# axiom_beta_plugin_module_TE0714_SDI_v0_9.net
KiCad netlist of a schematic drawn in EAGLE
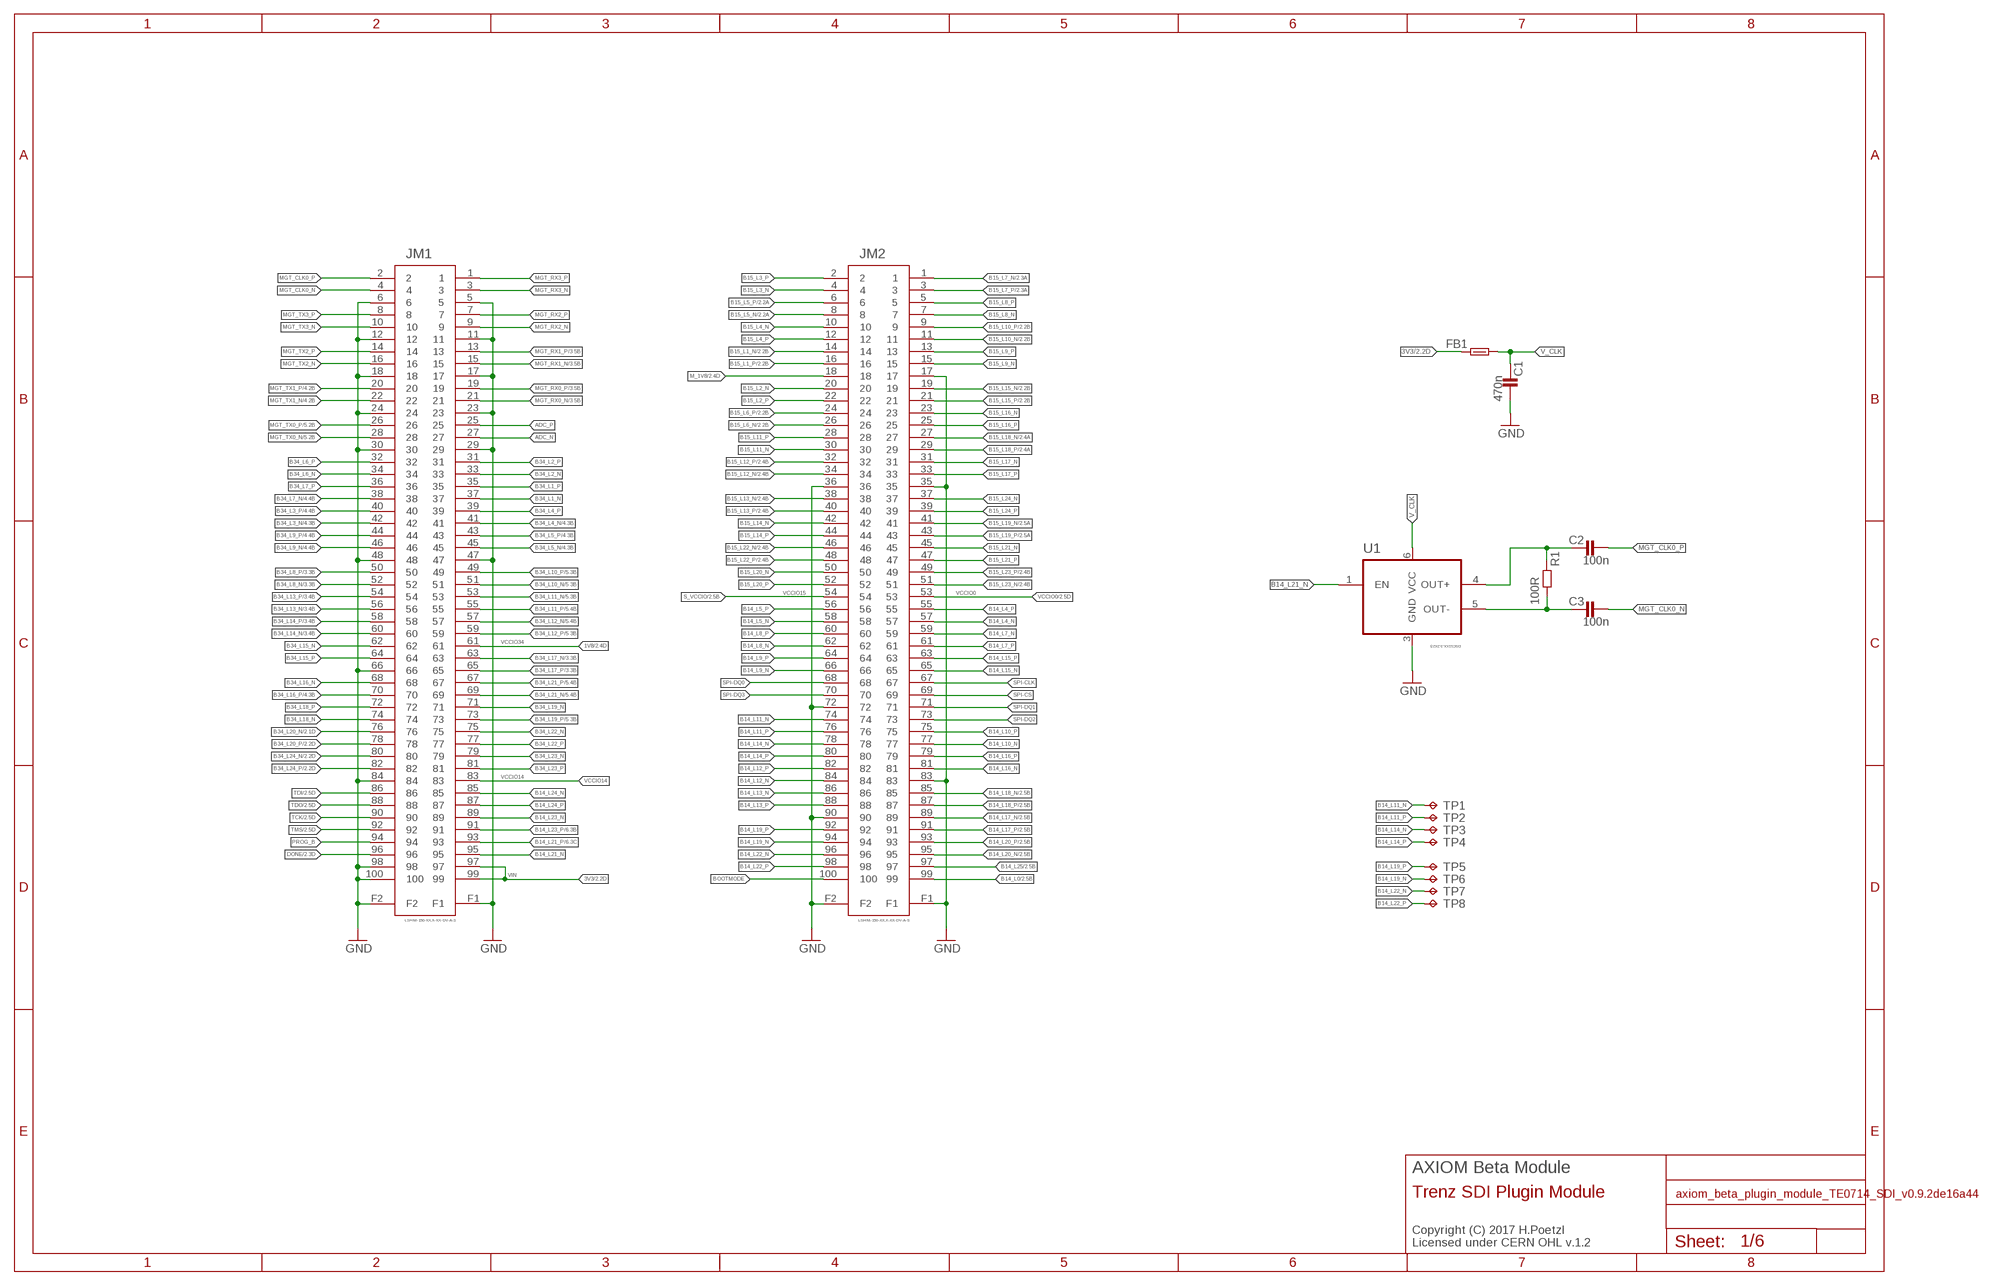
[diagram p0: schematic, sheet 1]
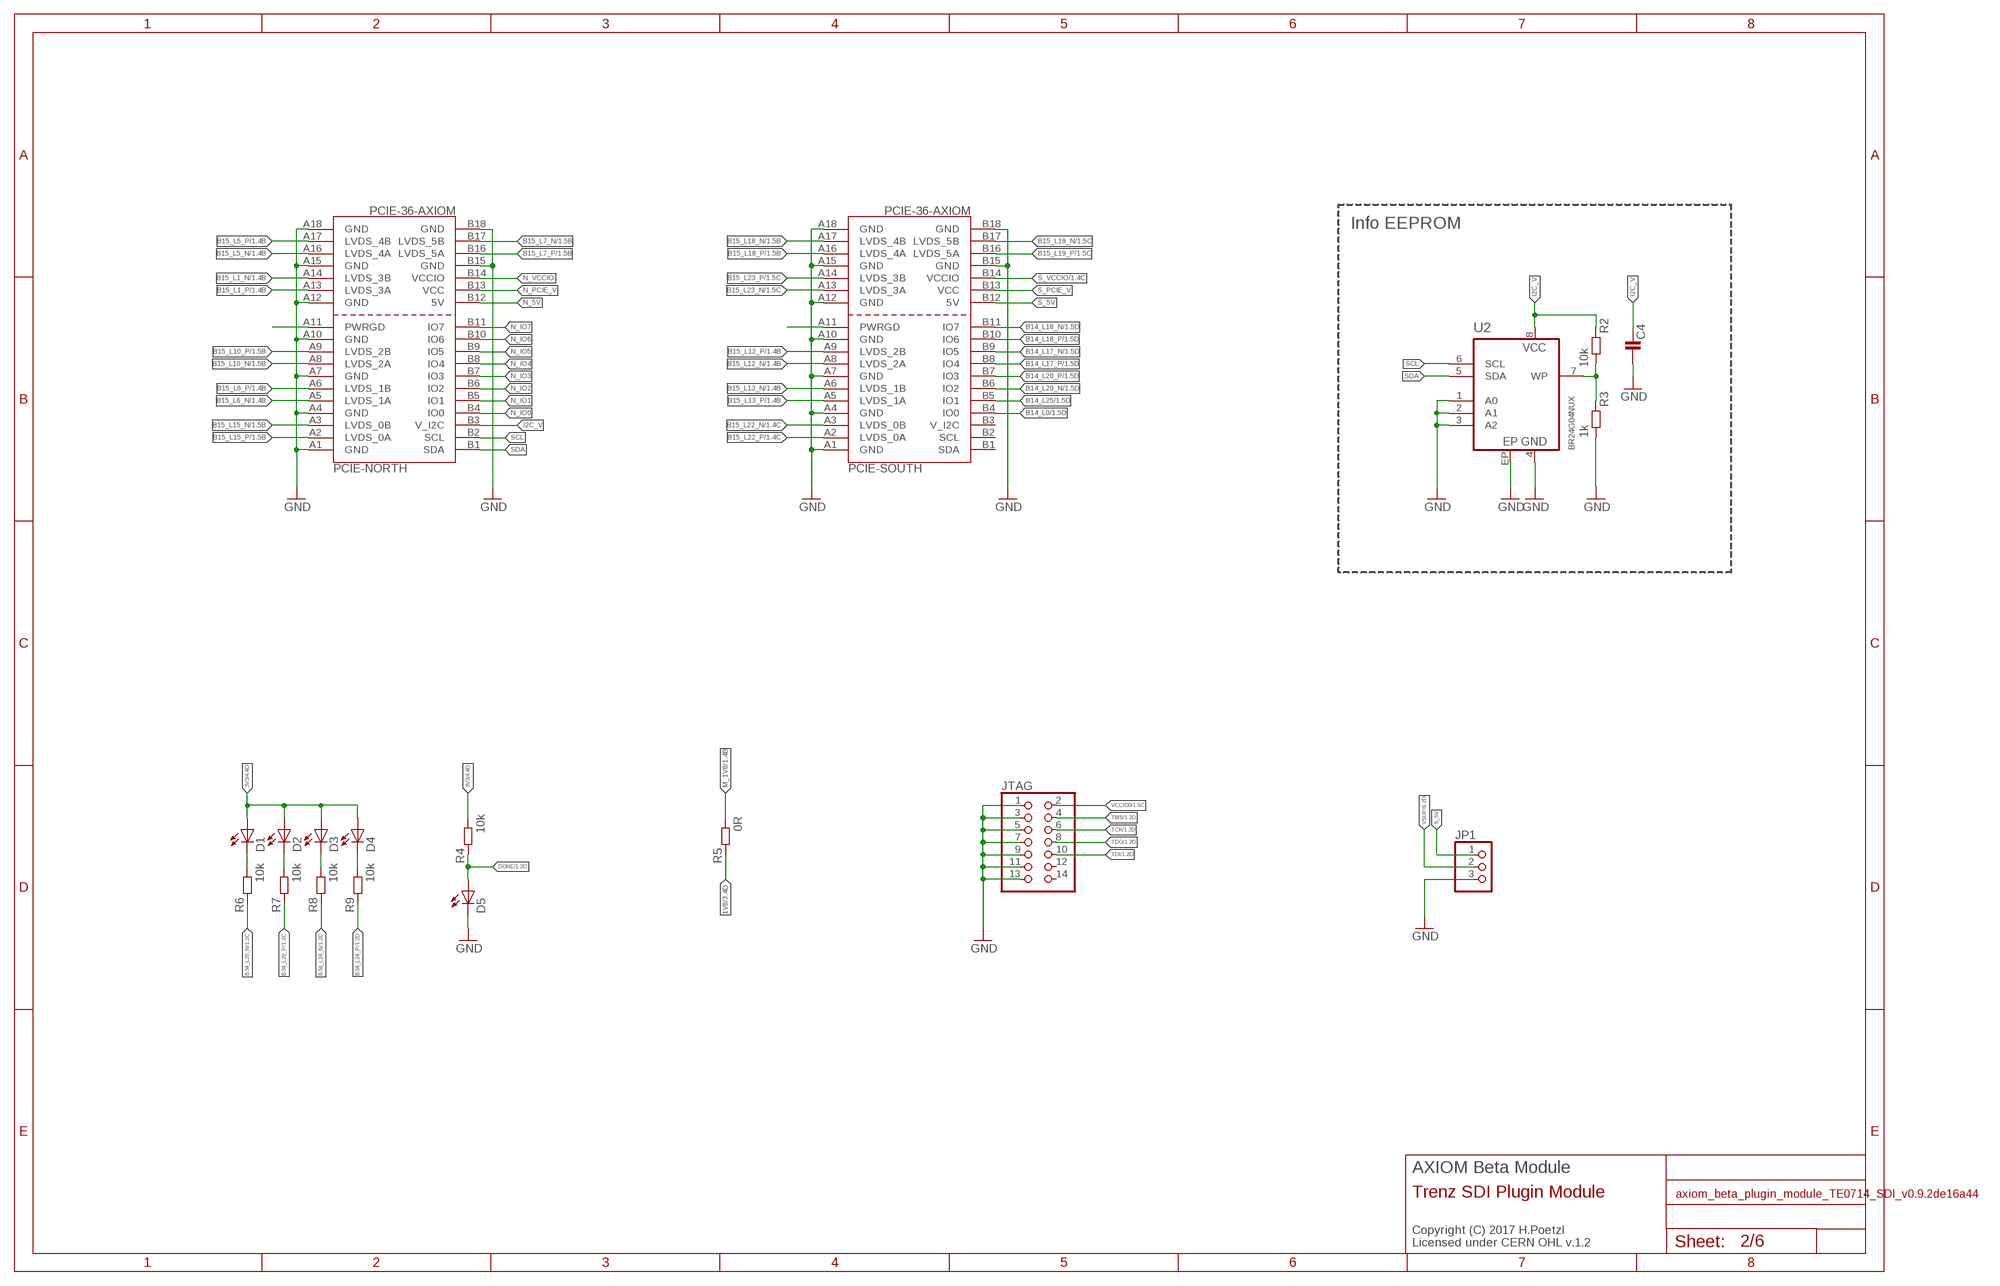
[diagram p1: schematic, sheet 2]
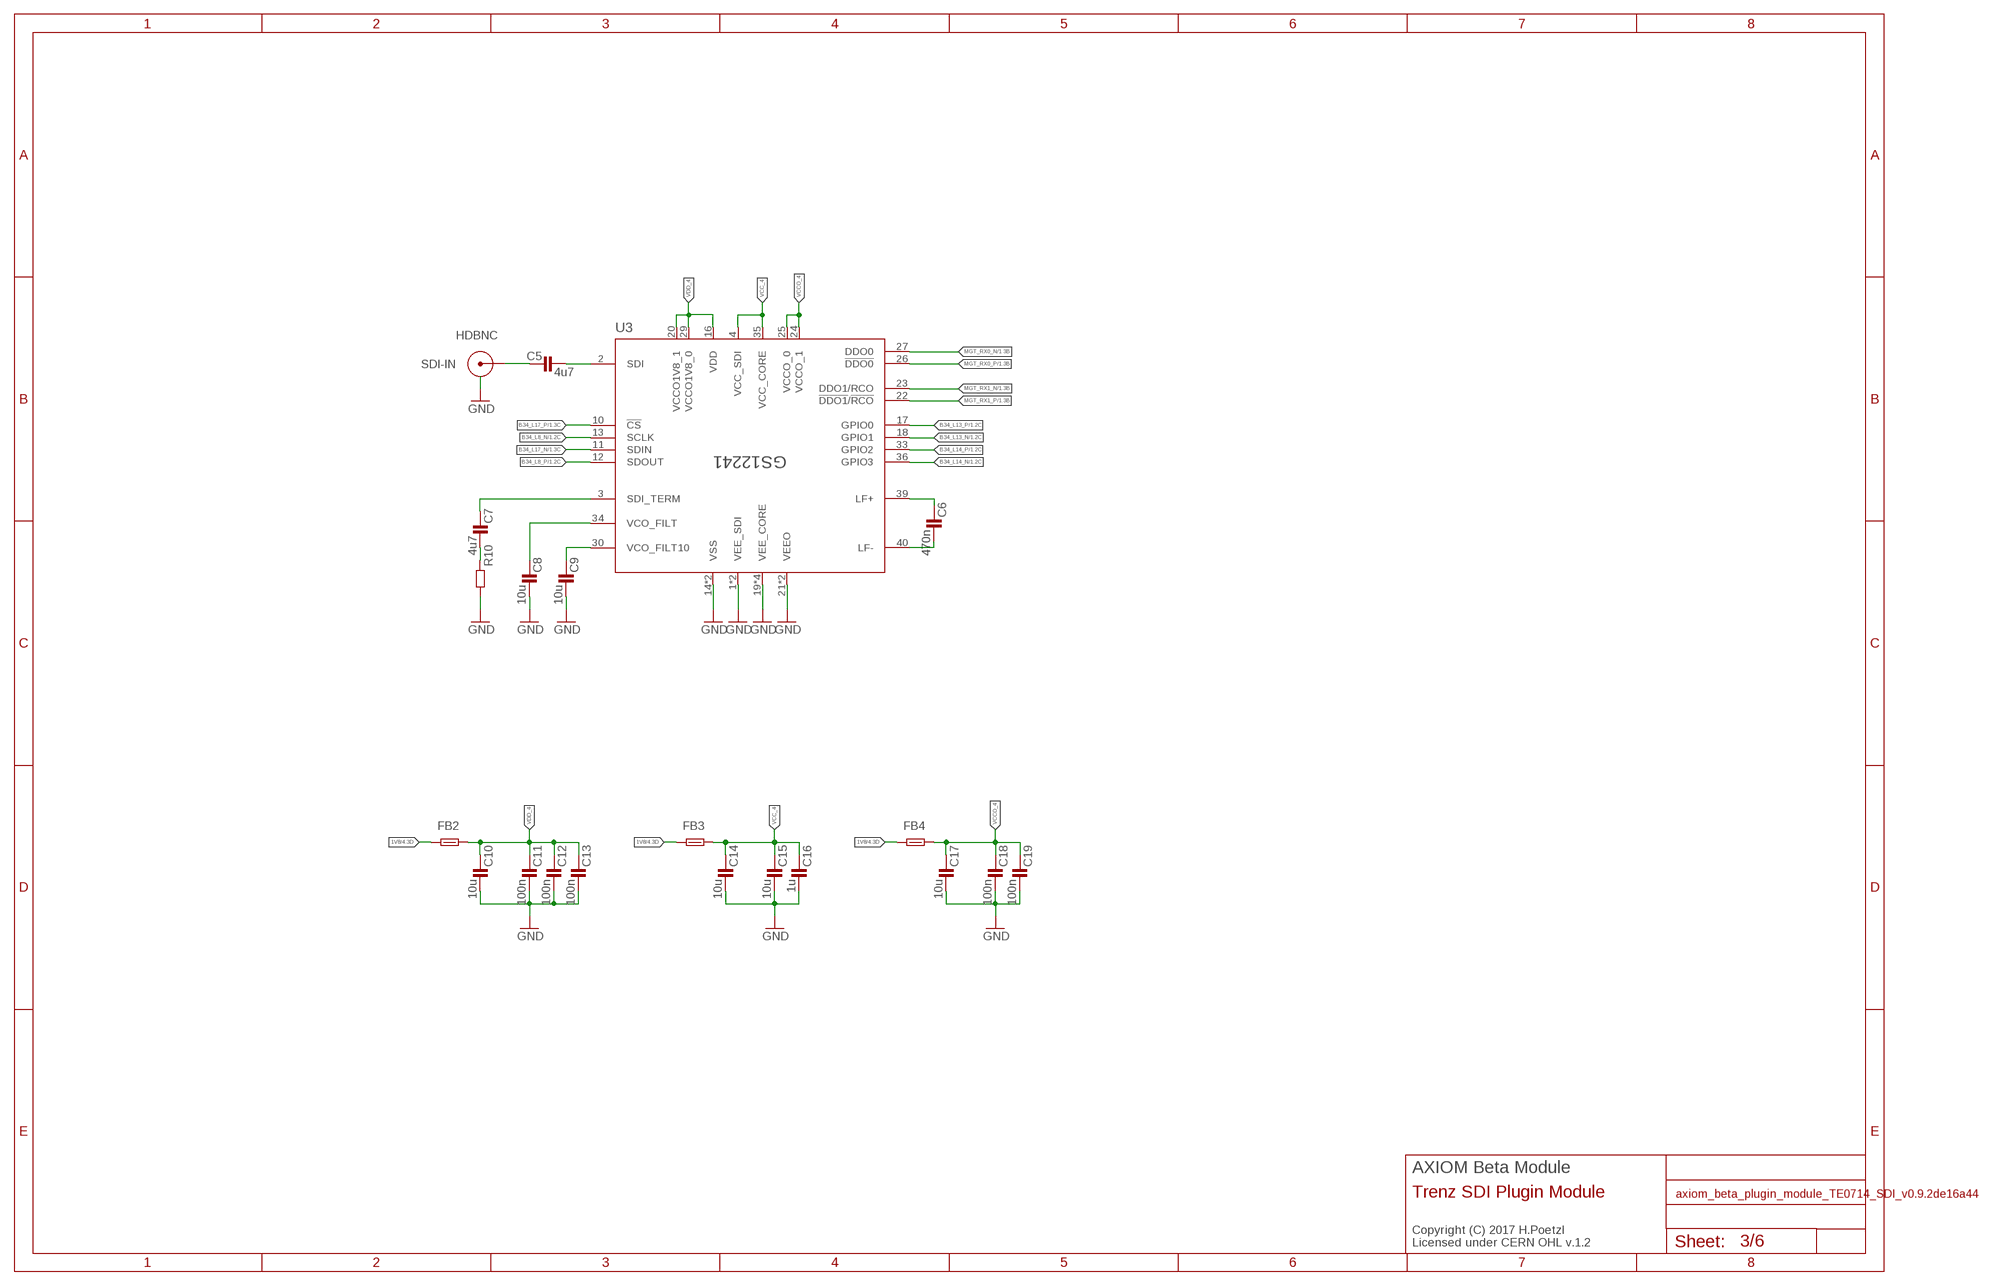
[diagram p2: schematic, sheet 3]
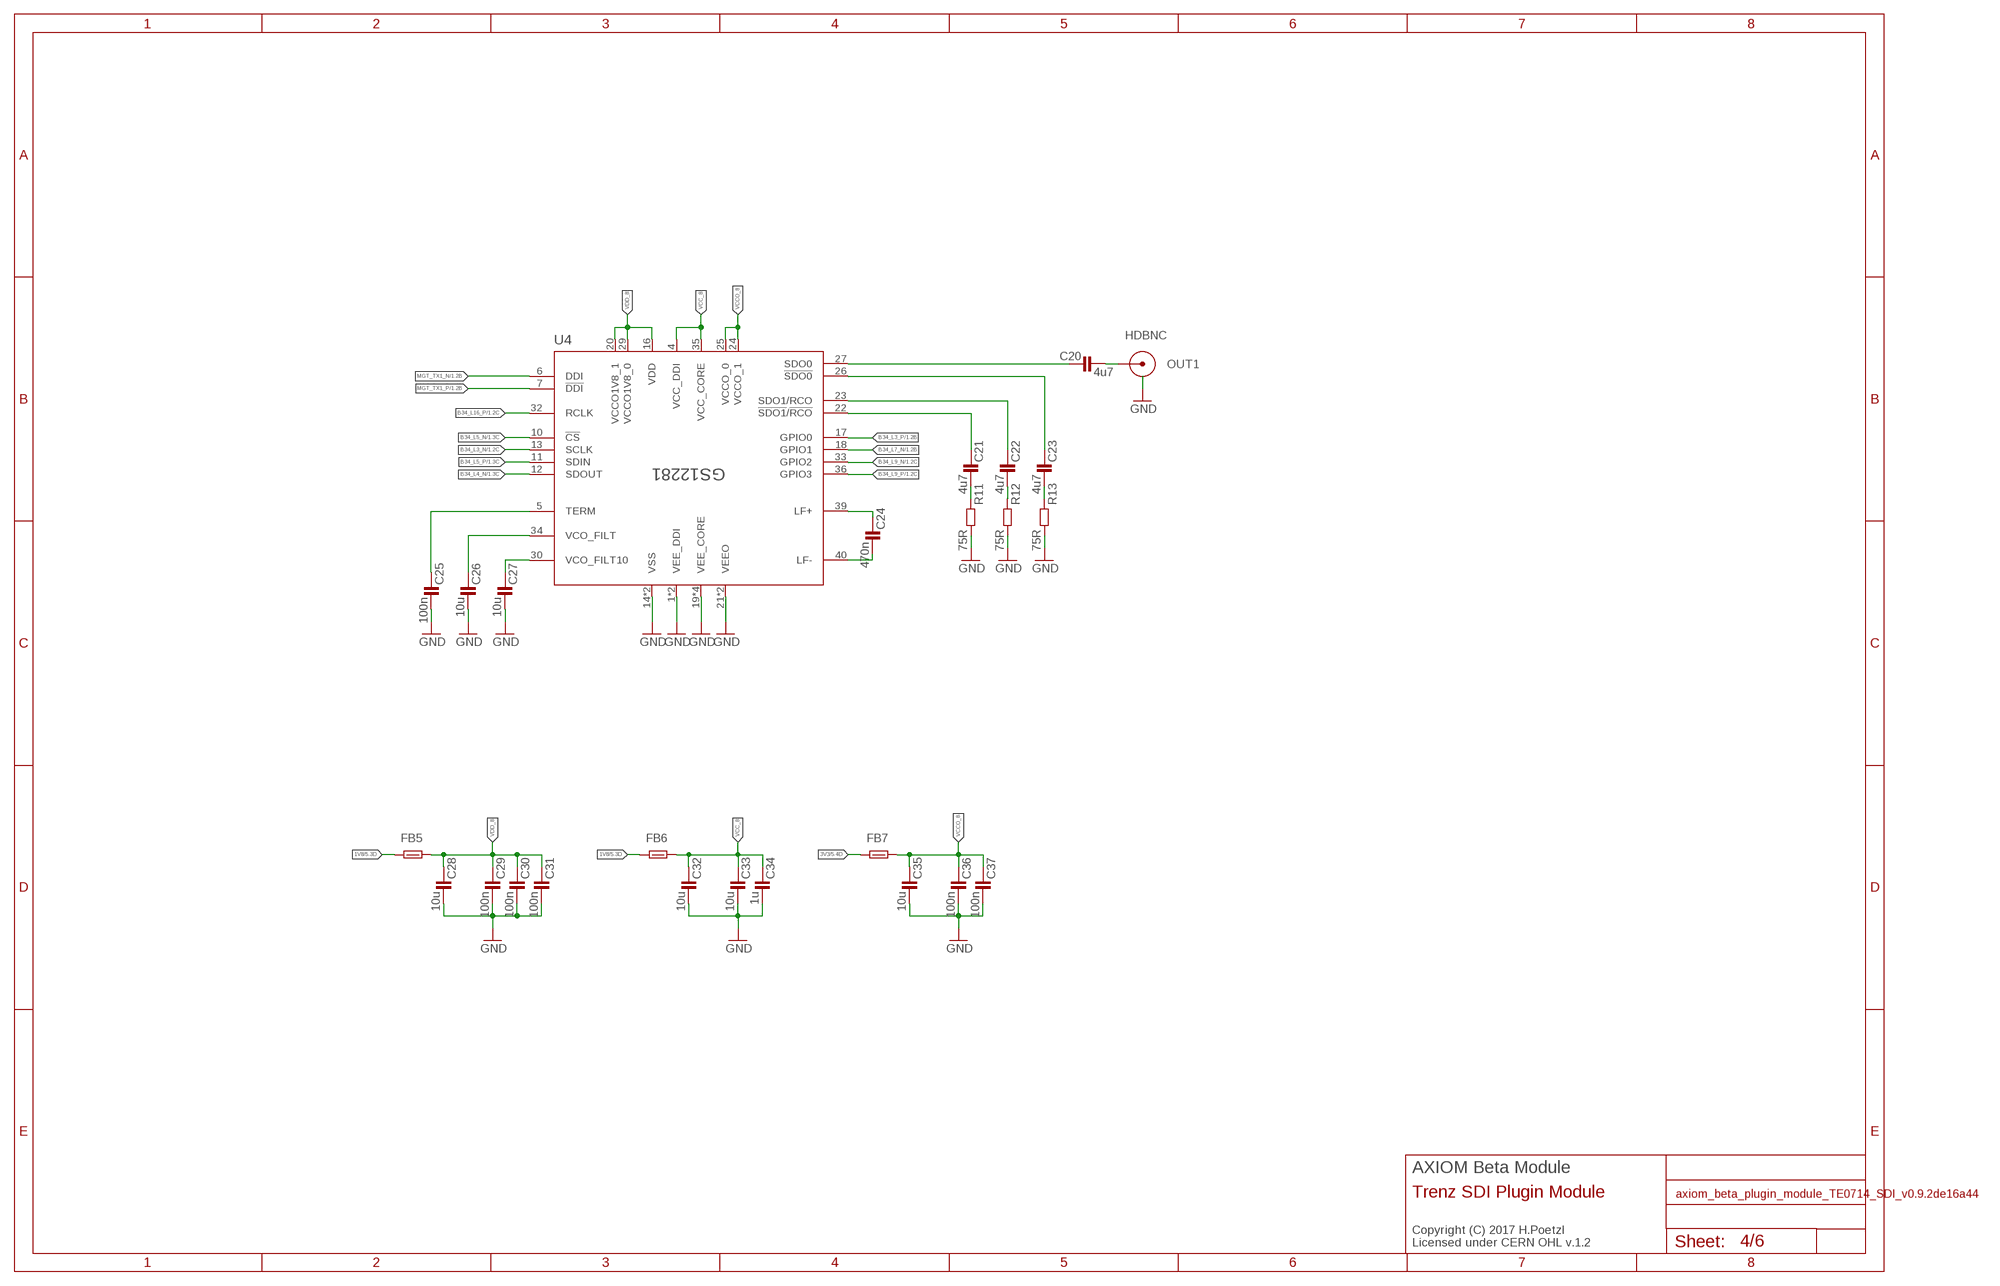
[diagram p3: schematic, sheet 4]
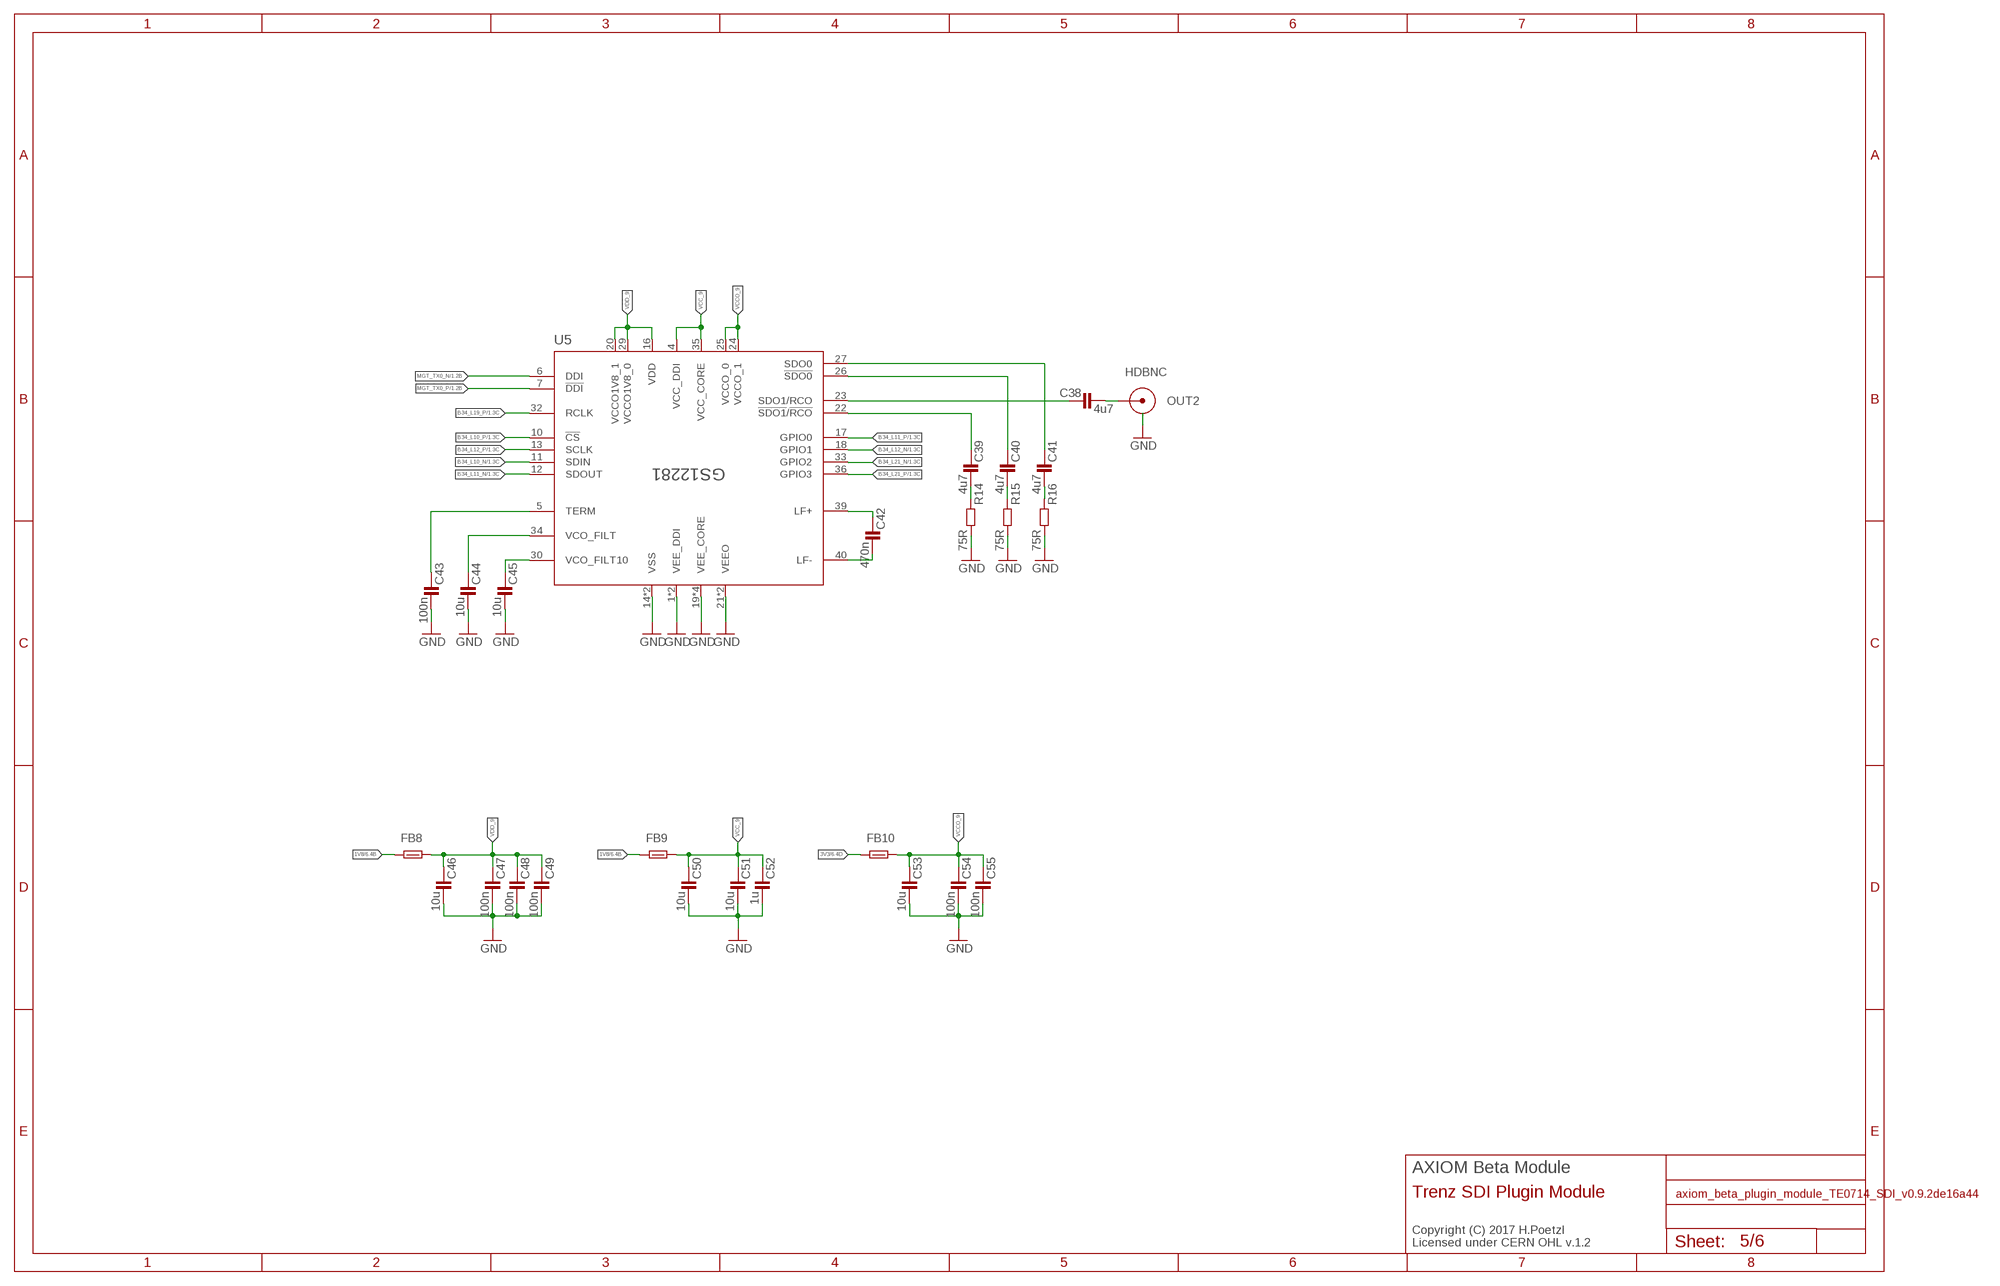
[diagram p4: schematic, sheet 5]
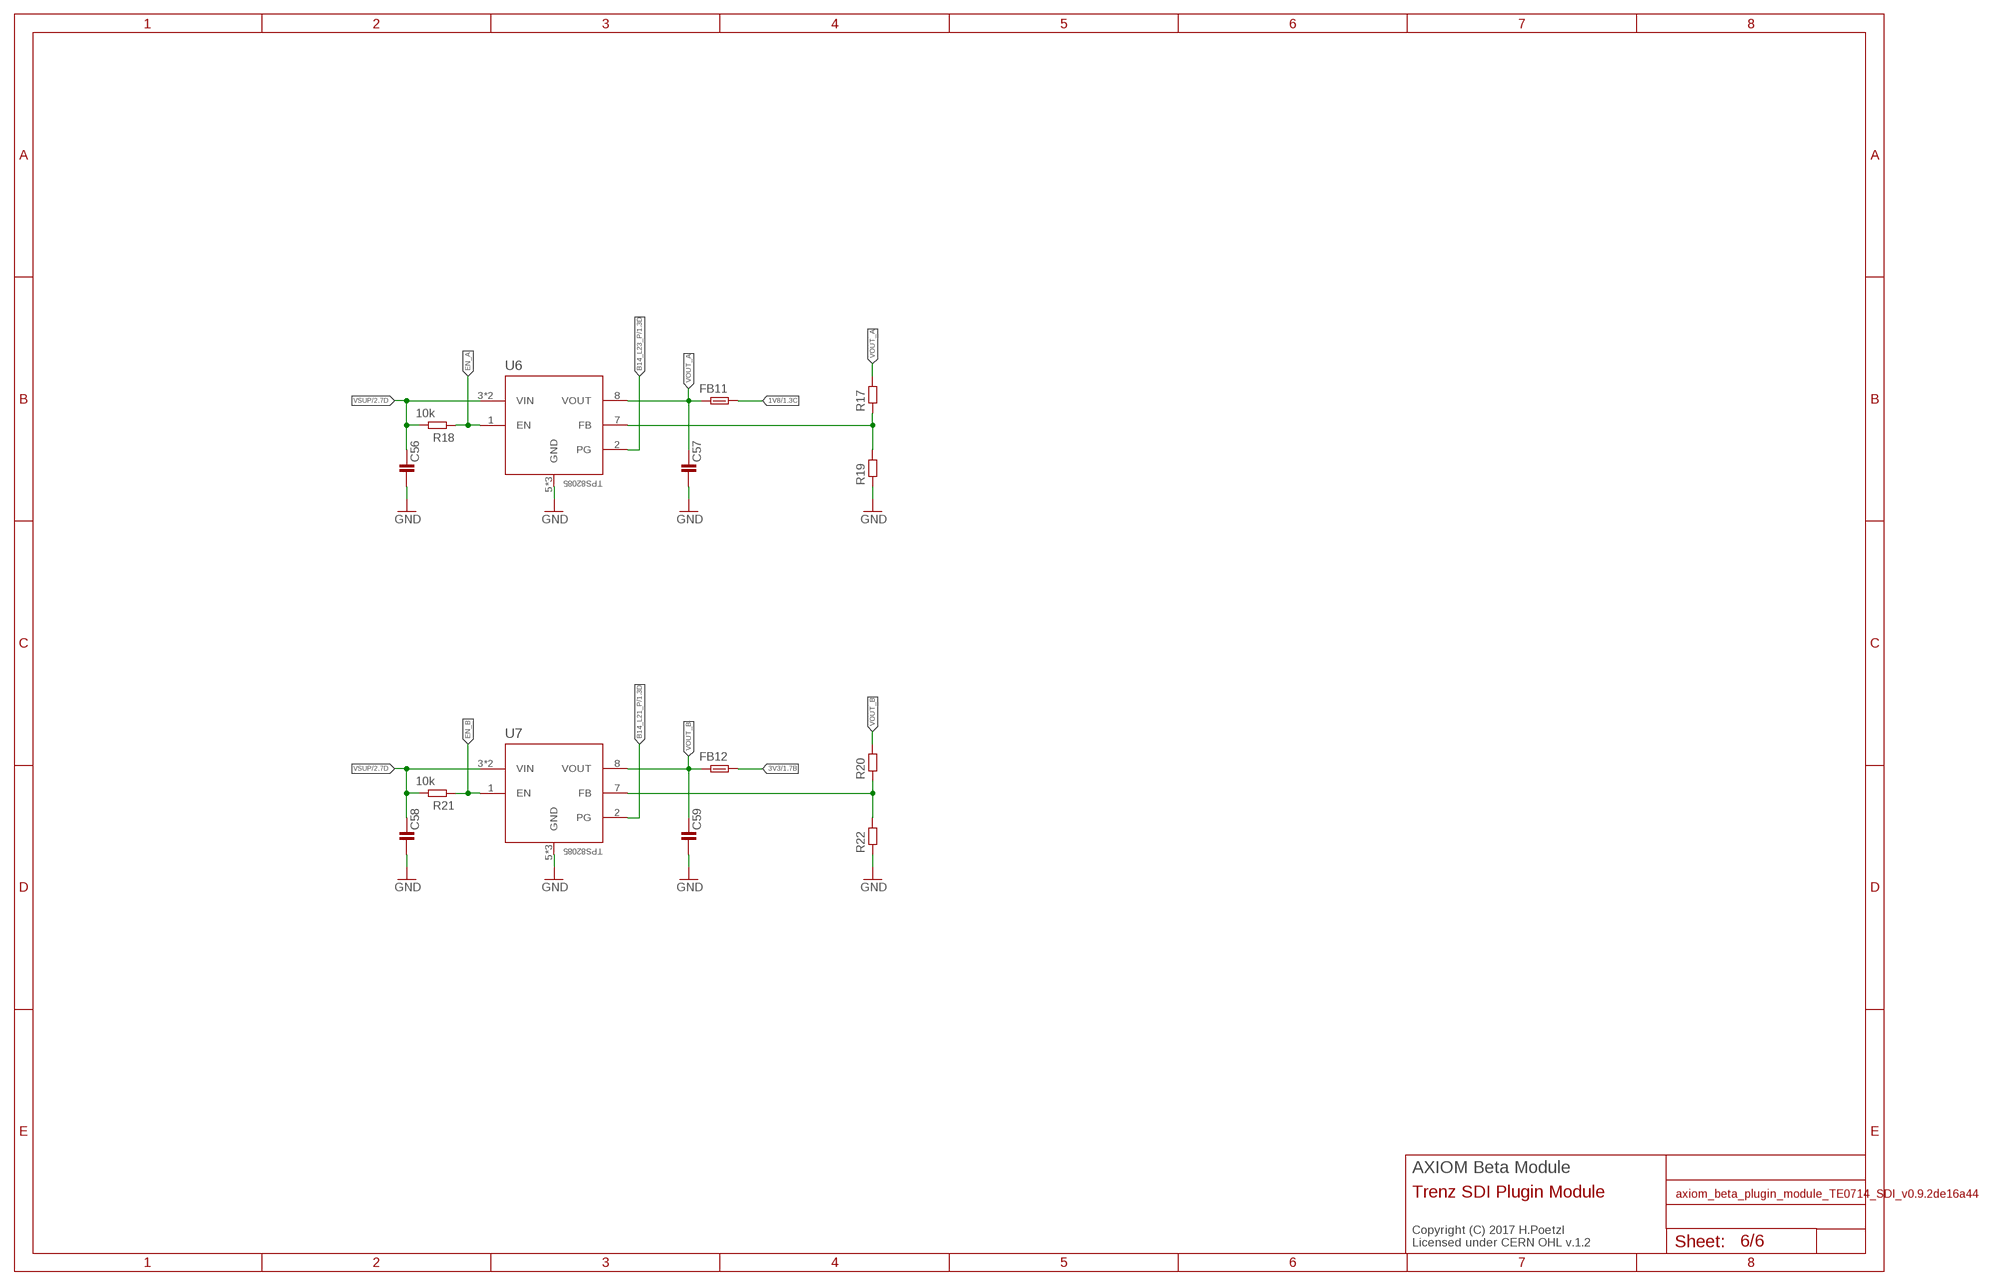
[diagram p5: schematic, sheet 6]

(export (version "E")
  (design (tool "Eeschema 10.0.6"))
  (components
    (comp (ref "C56")
      (value "C0603-C")
      (footprint "eagle-import:0603-C")
      (libsource (lib "eagle-import") (part "C0603-C"))
    )
    (comp (ref "C57")
      (value "C0603-C")
      (footprint "eagle-import:0603-C")
      (libsource (lib "eagle-import") (part "C0603-C"))
    )
    (comp (ref "C58")
      (value "C0603-C")
      (footprint "eagle-import:0603-C")
      (libsource (lib "eagle-import") (part "C0603-C"))
    )
    (comp (ref "C59")
      (value "C0603-C")
      (footprint "eagle-import:0603-C")
      (libsource (lib "eagle-import") (part "C0603-C"))
    )
    (comp (ref "FB11")
      (value "FB0603-C")
      (footprint "eagle-import:0603-C")
      (libsource (lib "eagle-import") (part "FB0603-C"))
    )
    (comp (ref "FB12")
      (value "FB0603-C")
      (footprint "eagle-import:0603-C")
      (libsource (lib "eagle-import") (part "FB0603-C"))
    )
    (comp (ref "R17")
      (value "R0201-C")
      (footprint "eagle-import:0201-C")
      (libsource (lib "eagle-import") (part "R0201-C"))
    )
    (comp (ref "R18")
      (value "10k")
      (footprint "eagle-import:0201-C")
      (libsource (lib "eagle-import") (part "R0201-C"))
    )
    (comp (ref "R19")
      (value "R0201-C")
      (footprint "eagle-import:0201-C")
      (libsource (lib "eagle-import") (part "R0201-C"))
    )
    (comp (ref "R20")
      (value "R0201-C")
      (footprint "eagle-import:0201-C")
      (libsource (lib "eagle-import") (part "R0201-C"))
    )
    (comp (ref "R21")
      (value "10k")
      (footprint "eagle-import:0201-C")
      (libsource (lib "eagle-import") (part "R0201-C"))
    )
    (comp (ref "R22")
      (value "R0201-C")
      (footprint "eagle-import:0201-C")
      (libsource (lib "eagle-import") (part "R0201-C"))
    )
    (comp (ref "U6")
      (value "TPS82085")
      (footprint "eagle-import:MICROSIP")
      (libsource (lib "eagle-import") (part "TPS82085"))
    )
    (comp (ref "U7")
      (value "TPS82085")
      (footprint "eagle-import:MICROSIP")
      (libsource (lib "eagle-import") (part "TPS82085"))
    )
    (comp (ref "C4")
      (value "C0402-B")
      (footprint "eagle-import:0402-B")
      (libsource (lib "eagle-import") (part "C0402-B"))
    )
    (comp (ref "D1")
      (value "LED")
      (footprint "eagle-import:CHIPLED_0603")
      (libsource (lib "eagle-import") (part "LED"))
    )
    (comp (ref "D2")
      (value "LED")
      (footprint "eagle-import:CHIPLED_0603")
      (libsource (lib "eagle-import") (part "LED"))
    )
    (comp (ref "D3")
      (value "LED")
      (footprint "eagle-import:CHIPLED_0603")
      (libsource (lib "eagle-import") (part "LED"))
    )
    (comp (ref "D4")
      (value "LED")
      (footprint "eagle-import:CHIPLED_0603")
      (libsource (lib "eagle-import") (part "LED"))
    )
    (comp (ref "D5")
      (value "LED")
      (footprint "eagle-import:CHIPLED_0603")
      (libsource (lib "eagle-import") (part "LED"))
    )
    (comp (ref "JP1")
      (value "PINHD-1X03_2.54-90°-S")
      (footprint "eagle-import:1X03_90-S")
      (libsource (lib "eagle-import") (part "PINHD-1X03_2.54-90°-S"))
    )
    (comp (ref "JTAG")
      (value "PINHD-2X07_2.00")
      (footprint "eagle-import:2X07M")
      (libsource (lib "eagle-import") (part "PINHD-2X07_2.00"))
    )
    (comp (ref "PCIE-NORTH")
      (value "PCIE-36-AXIOM")
      (footprint "eagle-import:PCIE-36-AXIOM")
      (libsource (lib "eagle-import") (part "PCIE-36-AXIOM"))
    )
    (comp (ref "PCIE-SOUTH")
      (value "PCIE-36-AXIOM")
      (footprint "eagle-import:PCIE-36-AXIOM")
      (libsource (lib "eagle-import") (part "PCIE-36-AXIOM"))
    )
    (comp (ref "R2")
      (value "10k")
      (footprint "eagle-import:0402-B")
      (libsource (lib "eagle-import") (part "R0402-B"))
    )
    (comp (ref "R3")
      (value "1k")
      (footprint "eagle-import:0402-B")
      (libsource (lib "eagle-import") (part "R0402-B"))
    )
    (comp (ref "R4")
      (value "10k")
      (footprint "eagle-import:0402-C")
      (libsource (lib "eagle-import") (part "R0402-C"))
    )
    (comp (ref "R5")
      (value "0R")
      (footprint "eagle-import:0402-C")
      (libsource (lib "eagle-import") (part "R0402-C"))
    )
    (comp (ref "R6")
      (value "10k")
      (footprint "eagle-import:0402-C")
      (libsource (lib "eagle-import") (part "R0402-C"))
    )
    (comp (ref "R7")
      (value "10k")
      (footprint "eagle-import:0402-C")
      (libsource (lib "eagle-import") (part "R0402-C"))
    )
    (comp (ref "R8")
      (value "10k")
      (footprint "eagle-import:0402-C")
      (libsource (lib "eagle-import") (part "R0402-C"))
    )
    (comp (ref "R9")
      (value "10k")
      (footprint "eagle-import:0402-C")
      (libsource (lib "eagle-import") (part "R0402-C"))
    )
    (comp (ref "U2")
      (value "BR24G04NUX")
      (footprint "eagle-import:DFN200X300X100-9N")
      (libsource (lib "eagle-import") (part "BR24G04NUX"))
    )
    (comp (ref "C38")
      (value "4u7")
      (footprint "eagle-import:0402-C")
      (libsource (lib "eagle-import") (part "C0402-C"))
    )
    (comp (ref "C39")
      (value "4u7")
      (footprint "eagle-import:0402-C")
      (libsource (lib "eagle-import") (part "C0402-C"))
    )
    (comp (ref "C40")
      (value "4u7")
      (footprint "eagle-import:0402-C")
      (libsource (lib "eagle-import") (part "C0402-C"))
    )
    (comp (ref "C41")
      (value "4u7")
      (footprint "eagle-import:0402-C")
      (libsource (lib "eagle-import") (part "C0402-C"))
    )
    (comp (ref "C42")
      (value "470n")
      (footprint "eagle-import:0201-C")
      (libsource (lib "eagle-import") (part "C0201-C"))
    )
    (comp (ref "C43")
      (value "100n")
      (footprint "eagle-import:0201-C")
      (libsource (lib "eagle-import") (part "C0201-C"))
    )
    (comp (ref "C44")
      (value "10u")
      (footprint "eagle-import:0402-C")
      (libsource (lib "eagle-import") (part "C0402-C"))
    )
    (comp (ref "C45")
      (value "10u")
      (footprint "eagle-import:0402-C")
      (libsource (lib "eagle-import") (part "C0402-C"))
    )
    (comp (ref "C46")
      (value "10u")
      (footprint "eagle-import:0402-C")
      (libsource (lib "eagle-import") (part "C0402-C"))
    )
    (comp (ref "C47")
      (value "100n")
      (footprint "eagle-import:0201-C")
      (libsource (lib "eagle-import") (part "C0201-C"))
    )
    (comp (ref "C48")
      (value "100n")
      (footprint "eagle-import:0201-C")
      (libsource (lib "eagle-import") (part "C0201-C"))
    )
    (comp (ref "C49")
      (value "100n")
      (footprint "eagle-import:0201-C")
      (libsource (lib "eagle-import") (part "C0201-C"))
    )
    (comp (ref "C50")
      (value "10u")
      (footprint "eagle-import:0402-C")
      (libsource (lib "eagle-import") (part "C0402-C"))
    )
    (comp (ref "C51")
      (value "10u")
      (footprint "eagle-import:0402-C")
      (libsource (lib "eagle-import") (part "C0402-C"))
    )
    (comp (ref "C52")
      (value "1u")
      (footprint "eagle-import:0201-C")
      (libsource (lib "eagle-import") (part "C0201-C"))
    )
    (comp (ref "C53")
      (value "10u")
      (footprint "eagle-import:0402-C")
      (libsource (lib "eagle-import") (part "C0402-C"))
    )
    (comp (ref "C54")
      (value "100n")
      (footprint "eagle-import:0201-C")
      (libsource (lib "eagle-import") (part "C0201-C"))
    )
    (comp (ref "C55")
      (value "100n")
      (footprint "eagle-import:0201-C")
      (libsource (lib "eagle-import") (part "C0201-C"))
    )
    (comp (ref "FB8")
      (value "FB0402-C")
      (footprint "eagle-import:0402-C")
      (libsource (lib "eagle-import") (part "FB0402-C"))
    )
    (comp (ref "FB9")
      (value "FB0402-C")
      (footprint "eagle-import:0402-C")
      (libsource (lib "eagle-import") (part "FB0402-C"))
    )
    (comp (ref "FB10")
      (value "FB0402-C")
      (footprint "eagle-import:0402-C")
      (libsource (lib "eagle-import") (part "FB0402-C"))
    )
    (comp (ref "OUT2")
      (value "HDBNC")
      (footprint "eagle-import:HDBNC_EDGE_2SIDE")
      (libsource (lib "eagle-import") (part "HDBNC"))
    )
    (comp (ref "R14")
      (value "75R")
      (footprint "eagle-import:0201-C")
      (libsource (lib "eagle-import") (part "R0201-C"))
    )
    (comp (ref "R15")
      (value "75R")
      (footprint "eagle-import:0201-C")
      (libsource (lib "eagle-import") (part "R0201-C"))
    )
    (comp (ref "R16")
      (value "75R")
      (footprint "eagle-import:0201-C")
      (libsource (lib "eagle-import") (part "R0201-C"))
    )
    (comp (ref "U5")
      (value "GS12281")
      (footprint "eagle-import:UQFN40P600X400X100-41N")
      (libsource (lib "eagle-import") (part "GS12281"))
    )
    (comp (ref "C5")
      (value "4u7")
      (footprint "eagle-import:0402-C")
      (libsource (lib "eagle-import") (part "C0402-C"))
    )
    (comp (ref "C6")
      (value "470n")
      (footprint "eagle-import:0201-C")
      (libsource (lib "eagle-import") (part "C0201-C"))
    )
    (comp (ref "C7")
      (value "4u7")
      (footprint "eagle-import:0402-C")
      (libsource (lib "eagle-import") (part "C0402-C"))
    )
    (comp (ref "C8")
      (value "10u")
      (footprint "eagle-import:0201-C")
      (libsource (lib "eagle-import") (part "C0201-C"))
    )
    (comp (ref "C9")
      (value "10u")
      (footprint "eagle-import:0402-C")
      (libsource (lib "eagle-import") (part "C0402-C"))
    )
    (comp (ref "C10")
      (value "10u")
      (footprint "eagle-import:0402-C")
      (libsource (lib "eagle-import") (part "C0402-C"))
    )
    (comp (ref "C11")
      (value "100n")
      (footprint "eagle-import:0201-C")
      (libsource (lib "eagle-import") (part "C0201-C"))
    )
    (comp (ref "C12")
      (value "100n")
      (footprint "eagle-import:0201-C")
      (libsource (lib "eagle-import") (part "C0201-C"))
    )
    (comp (ref "C13")
      (value "100n")
      (footprint "eagle-import:0201-C")
      (libsource (lib "eagle-import") (part "C0201-C"))
    )
    (comp (ref "C14")
      (value "10u")
      (footprint "eagle-import:0402-C")
      (libsource (lib "eagle-import") (part "C0402-C"))
    )
    (comp (ref "C15")
      (value "10u")
      (footprint "eagle-import:0402-C")
      (libsource (lib "eagle-import") (part "C0402-C"))
    )
    (comp (ref "C16")
      (value "1u")
      (footprint "eagle-import:0201-C")
      (libsource (lib "eagle-import") (part "C0201-C"))
    )
    (comp (ref "C17")
      (value "10u")
      (footprint "eagle-import:0402-C")
      (libsource (lib "eagle-import") (part "C0402-C"))
    )
    (comp (ref "C18")
      (value "100n")
      (footprint "eagle-import:0201-C")
      (libsource (lib "eagle-import") (part "C0201-C"))
    )
    (comp (ref "C19")
      (value "100n")
      (footprint "eagle-import:0201-C")
      (libsource (lib "eagle-import") (part "C0201-C"))
    )
    (comp (ref "FB2")
      (value "FB0402-C")
      (footprint "eagle-import:0402-C")
      (libsource (lib "eagle-import") (part "FB0402-C"))
    )
    (comp (ref "FB3")
      (value "FB0402-C")
      (footprint "eagle-import:0402-C")
      (libsource (lib "eagle-import") (part "FB0402-C"))
    )
    (comp (ref "FB4")
      (value "FB0402-C")
      (footprint "eagle-import:0402-C")
      (libsource (lib "eagle-import") (part "FB0402-C"))
    )
    (comp (ref "R10")
      (value "R0201-C")
      (footprint "eagle-import:0201-C")
      (libsource (lib "eagle-import") (part "R0201-C"))
    )
    (comp (ref "SDI-IN")
      (value "HDBNC")
      (footprint "eagle-import:HDBNC_EDGE_2SIDE")
      (libsource (lib "eagle-import") (part "HDBNC"))
    )
    (comp (ref "U3")
      (value "GS12241")
      (footprint "eagle-import:UQFN40P600X400X100-41N")
      (libsource (lib "eagle-import") (part "GS12241"))
    )
    (comp (ref "C1")
      (value "470n")
      (footprint "eagle-import:0402-C")
      (libsource (lib "eagle-import") (part "C0402-C"))
    )
    (comp (ref "C2")
      (value "100n")
      (footprint "eagle-import:0201-C")
      (libsource (lib "eagle-import") (part "C0201-C"))
    )
    (comp (ref "C3")
      (value "100n")
      (footprint "eagle-import:0201-C")
      (libsource (lib "eagle-import") (part "C0201-C"))
    )
    (comp (ref "FB1")
      (value "FB0402-C")
      (footprint "eagle-import:0402-C")
      (libsource (lib "eagle-import") (part "FB0402-C"))
    )
    (comp (ref "JM1")
      (value "LSHM-150-XX.X-XX-DV-A-S")
      (footprint "eagle-import:LSHM-150-XX.X-XX-DV-A-S")
      (libsource (lib "eagle-import") (part "LSHM-150-XX.X-XX-DV-A-S"))
    )
    (comp (ref "JM2")
      (value "LSHM-150-XX.X-XX-DV-A-S")
      (footprint "eagle-import:LSHM-150-XX.X-XX-DV-A-S")
      (libsource (lib "eagle-import") (part "LSHM-150-XX.X-XX-DV-A-S"))
    )
    (comp (ref "R1")
      (value "100R")
      (footprint "eagle-import:0201-C")
      (libsource (lib "eagle-import") (part "R0201-C"))
    )
    (comp (ref "TP1")
      (value "TPTP08R")
      (footprint "eagle-import:TP08R")
      (libsource (lib "eagle-import") (part "TPTP08R"))
    )
    (comp (ref "TP2")
      (value "TPTP08R")
      (footprint "eagle-import:TP08R")
      (libsource (lib "eagle-import") (part "TPTP08R"))
    )
    (comp (ref "TP3")
      (value "TPTP08R")
      (footprint "eagle-import:TP08R")
      (libsource (lib "eagle-import") (part "TPTP08R"))
    )
    (comp (ref "TP4")
      (value "TPTP08R")
      (footprint "eagle-import:TP08R")
      (libsource (lib "eagle-import") (part "TPTP08R"))
    )
    (comp (ref "TP5")
      (value "TPTP10R")
      (footprint "eagle-import:TP10R")
      (libsource (lib "eagle-import") (part "TPTP10R"))
    )
    (comp (ref "TP6")
      (value "TPTP10R")
      (footprint "eagle-import:TP10R")
      (libsource (lib "eagle-import") (part "TPTP10R"))
    )
    (comp (ref "TP7")
      (value "TPTP10R")
      (footprint "eagle-import:TP10R")
      (libsource (lib "eagle-import") (part "TPTP10R"))
    )
    (comp (ref "TP8")
      (value "TPTP10R")
      (footprint "eagle-import:TP10R")
      (libsource (lib "eagle-import") (part "TPTP10R"))
    )
    (comp (ref "U1")
      (value "DSC11XX-3.2X2.5")
      (footprint "eagle-import:3.2X2.5")
      (libsource (lib "eagle-import") (part "DSC11XX-3.2X2.5"))
    )
    (comp (ref "C20")
      (value "4u7")
      (footprint "eagle-import:0402-C")
      (libsource (lib "eagle-import") (part "C0402-C"))
    )
    (comp (ref "C21")
      (value "4u7")
      (footprint "eagle-import:0402-C")
      (libsource (lib "eagle-import") (part "C0402-C"))
    )
    (comp (ref "C22")
      (value "4u7")
      (footprint "eagle-import:0402-C")
      (libsource (lib "eagle-import") (part "C0402-C"))
    )
    (comp (ref "C23")
      (value "4u7")
      (footprint "eagle-import:0402-C")
      (libsource (lib "eagle-import") (part "C0402-C"))
    )
    (comp (ref "C24")
      (value "470n")
      (footprint "eagle-import:0201-C")
      (libsource (lib "eagle-import") (part "C0201-C"))
    )
    (comp (ref "C25")
      (value "100n")
      (footprint "eagle-import:0201-C")
      (libsource (lib "eagle-import") (part "C0201-C"))
    )
    (comp (ref "C26")
      (value "10u")
      (footprint "eagle-import:0201-C")
      (libsource (lib "eagle-import") (part "C0201-C"))
    )
    (comp (ref "C27")
      (value "10u")
      (footprint "eagle-import:0402-C")
      (libsource (lib "eagle-import") (part "C0402-C"))
    )
    (comp (ref "C28")
      (value "10u")
      (footprint "eagle-import:0402-C")
      (libsource (lib "eagle-import") (part "C0402-C"))
    )
    (comp (ref "C29")
      (value "100n")
      (footprint "eagle-import:0201-C")
      (libsource (lib "eagle-import") (part "C0201-C"))
    )
    (comp (ref "C30")
      (value "100n")
      (footprint "eagle-import:0201-C")
      (libsource (lib "eagle-import") (part "C0201-C"))
    )
    (comp (ref "C31")
      (value "100n")
      (footprint "eagle-import:0201-C")
      (libsource (lib "eagle-import") (part "C0201-C"))
    )
    (comp (ref "C32")
      (value "10u")
      (footprint "eagle-import:0402-C")
      (libsource (lib "eagle-import") (part "C0402-C"))
    )
    (comp (ref "C33")
      (value "10u")
      (footprint "eagle-import:0402-C")
      (libsource (lib "eagle-import") (part "C0402-C"))
    )
    (comp (ref "C34")
      (value "1u")
      (footprint "eagle-import:0201-C")
      (libsource (lib "eagle-import") (part "C0201-C"))
    )
    (comp (ref "C35")
      (value "10u")
      (footprint "eagle-import:0402-C")
      (libsource (lib "eagle-import") (part "C0402-C"))
    )
    (comp (ref "C36")
      (value "100n")
      (footprint "eagle-import:0201-C")
      (libsource (lib "eagle-import") (part "C0201-C"))
    )
    (comp (ref "C37")
      (value "100n")
      (footprint "eagle-import:0201-C")
      (libsource (lib "eagle-import") (part "C0201-C"))
    )
    (comp (ref "FB5")
      (value "FB0402-C")
      (footprint "eagle-import:0402-C")
      (libsource (lib "eagle-import") (part "FB0402-C"))
    )
    (comp (ref "FB6")
      (value "FB0402-C")
      (footprint "eagle-import:0402-C")
      (libsource (lib "eagle-import") (part "FB0402-C"))
    )
    (comp (ref "FB7")
      (value "FB0402-C")
      (footprint "eagle-import:0402-C")
      (libsource (lib "eagle-import") (part "FB0402-C"))
    )
    (comp (ref "OUT1")
      (value "HDBNC")
      (footprint "eagle-import:HDBNC_EDGE_2SIDE")
      (libsource (lib "eagle-import") (part "HDBNC"))
    )
    (comp (ref "R11")
      (value "75R")
      (footprint "eagle-import:0201-C")
      (libsource (lib "eagle-import") (part "R0201-C"))
    )
    (comp (ref "R12")
      (value "75R")
      (footprint "eagle-import:0201-C")
      (libsource (lib "eagle-import") (part "R0201-C"))
    )
    (comp (ref "R13")
      (value "75R")
      (footprint "eagle-import:0201-C")
      (libsource (lib "eagle-import") (part "R0201-C"))
    )
    (comp (ref "U4")
      (value "GS12281")
      (footprint "eagle-import:UQFN40P600X400X100-41N")
      (libsource (lib "eagle-import") (part "GS12281"))
    )
  )
  (nets
    (net (code "1") (name "1V8") (class "Default")
      (node (ref "FB11") (pin "2") (pinfunction "2_2") (pintype "passive"))
      (node (ref "FB2") (pin "1") (pinfunction "1_1") (pintype "passive"))
      (node (ref "FB3") (pin "1") (pinfunction "1_1") (pintype "passive"))
      (node (ref "FB4") (pin "1") (pinfunction "1_1") (pintype "passive"))
      (node (ref "FB5") (pin "1") (pinfunction "1_1") (pintype "passive"))
      (node (ref "FB6") (pin "1") (pinfunction "1_1") (pintype "passive"))
      (node (ref "FB8") (pin "1") (pinfunction "1_1") (pintype "passive"))
      (node (ref "FB9") (pin "1") (pinfunction "1_1") (pintype "passive"))
      (node (ref "JM1") (pin "61") (pinfunction "61_61") (pintype "bidirectional"))
      (node (ref "R5") (pin "1") (pinfunction "1_1") (pintype "passive"))
    )
    (net (code "2") (name "3V3") (class "Default")
      (node (ref "D1") (pin "A") (pinfunction "A_A") (pintype "passive"))
      (node (ref "D2") (pin "A") (pinfunction "A_A") (pintype "passive"))
      (node (ref "D3") (pin "A") (pinfunction "A_A") (pintype "passive"))
      (node (ref "D4") (pin "A") (pinfunction "A_A") (pintype "passive"))
      (node (ref "FB1") (pin "1") (pinfunction "1_1") (pintype "passive"))
      (node (ref "FB10") (pin "1") (pinfunction "1_1") (pintype "passive"))
      (node (ref "FB12") (pin "2") (pinfunction "2_2") (pintype "passive"))
      (node (ref "FB7") (pin "1") (pinfunction "1_1") (pintype "passive"))
      (node (ref "JM1") (pin "97") (pinfunction "97_97") (pintype "bidirectional"))
      (node (ref "JM1") (pin "99") (pinfunction "99_99") (pintype "bidirectional"))
      (node (ref "R4") (pin "2") (pinfunction "2_2") (pintype "passive"))
    )
    (net (code "3") (name "ADC_N") (class "Default")
      (node (ref "JM1") (pin "27") (pinfunction "27_27") (pintype "bidirectional"))
    )
    (net (code "4") (name "ADC_P") (class "Default")
      (node (ref "JM1") (pin "25") (pinfunction "25_25") (pintype "bidirectional"))
    )
    (net (code "5") (name "B14_L0") (class "Default")
      (node (ref "JM2") (pin "99") (pinfunction "99_99") (pintype "bidirectional"))
      (node (ref "PCIE-SOUTH") (pin "B4") (pinfunction "IO0_B4") (pintype "passive"))
    )
    (net (code "6") (name "B14_L4_N") (class "Default")
      (node (ref "JM2") (pin "57") (pinfunction "57_57") (pintype "bidirectional"))
    )
    (net (code "7") (name "B14_L4_P") (class "Default")
      (node (ref "JM2") (pin "55") (pinfunction "55_55") (pintype "bidirectional"))
    )
    (net (code "8") (name "B14_L5_N") (class "Default")
      (node (ref "JM2") (pin "58") (pinfunction "58_58") (pintype "bidirectional"))
    )
    (net (code "9") (name "B14_L5_P") (class "Default")
      (node (ref "JM2") (pin "56") (pinfunction "56_56") (pintype "bidirectional"))
    )
    (net (code "10") (name "B14_L7_N") (class "Default")
      (node (ref "JM2") (pin "59") (pinfunction "59_59") (pintype "bidirectional"))
    )
    (net (code "11") (name "B14_L7_P") (class "Default")
      (node (ref "JM2") (pin "61") (pinfunction "61_61") (pintype "bidirectional"))
    )
    (net (code "12") (name "B14_L8_N") (class "Default")
      (node (ref "JM2") (pin "62") (pinfunction "62_62") (pintype "bidirectional"))
    )
    (net (code "13") (name "B14_L8_P") (class "Default")
      (node (ref "JM2") (pin "60") (pinfunction "60_60") (pintype "bidirectional"))
    )
    (net (code "14") (name "B14_L9_N") (class "Default")
      (node (ref "JM2") (pin "66") (pinfunction "66_66") (pintype "bidirectional"))
    )
    (net (code "15") (name "B14_L9_P") (class "Default")
      (node (ref "JM2") (pin "64") (pinfunction "64_64") (pintype "bidirectional"))
    )
    (net (code "16") (name "B14_L10_N") (class "Default")
      (node (ref "JM2") (pin "77") (pinfunction "77_77") (pintype "bidirectional"))
    )
    (net (code "17") (name "B14_L10_P") (class "Default")
      (node (ref "JM2") (pin "75") (pinfunction "75_75") (pintype "bidirectional"))
    )
    (net (code "18") (name "B14_L11_N") (class "Default")
      (node (ref "JM2") (pin "74") (pinfunction "74_74") (pintype "bidirectional"))
      (node (ref "TP1") (pin "TP") (pinfunction "TP_TP") (pintype "input"))
    )
    (net (code "19") (name "B14_L11_P") (class "Default")
      (node (ref "JM2") (pin "76") (pinfunction "76_76") (pintype "bidirectional"))
      (node (ref "TP2") (pin "TP") (pinfunction "TP_TP") (pintype "input"))
    )
    (net (code "20") (name "B14_L12_N") (class "Default")
      (node (ref "JM2") (pin "84") (pinfunction "84_84") (pintype "bidirectional"))
    )
    (net (code "21") (name "B14_L12_P") (class "Default")
      (node (ref "JM2") (pin "82") (pinfunction "82_82") (pintype "bidirectional"))
    )
    (net (code "22") (name "B14_L13_N") (class "Default")
      (node (ref "JM2") (pin "86") (pinfunction "86_86") (pintype "bidirectional"))
    )
    (net (code "23") (name "B14_L13_P") (class "Default")
      (node (ref "JM2") (pin "88") (pinfunction "88_88") (pintype "bidirectional"))
    )
    (net (code "24") (name "B14_L14_N") (class "Default")
      (node (ref "JM2") (pin "78") (pinfunction "78_78") (pintype "bidirectional"))
      (node (ref "TP3") (pin "TP") (pinfunction "TP_TP") (pintype "input"))
    )
    (net (code "25") (name "B14_L14_P") (class "Default")
      (node (ref "JM2") (pin "80") (pinfunction "80_80") (pintype "bidirectional"))
      (node (ref "TP4") (pin "TP") (pinfunction "TP_TP") (pintype "input"))
    )
    (net (code "26") (name "B14_L15_N") (class "Default")
      (node (ref "JM2") (pin "65") (pinfunction "65_65") (pintype "bidirectional"))
    )
    (net (code "27") (name "B14_L15_P") (class "Default")
      (node (ref "JM2") (pin "63") (pinfunction "63_63") (pintype "bidirectional"))
    )
    (net (code "28") (name "B14_L16_N") (class "Default")
      (node (ref "JM2") (pin "81") (pinfunction "81_81") (pintype "bidirectional"))
    )
    (net (code "29") (name "B14_L16_P") (class "Default")
      (node (ref "JM2") (pin "79") (pinfunction "79_79") (pintype "bidirectional"))
    )
    (net (code "30") (name "B14_L17_N") (class "Default")
      (node (ref "JM2") (pin "89") (pinfunction "89_89") (pintype "bidirectional"))
      (node (ref "PCIE-SOUTH") (pin "B9") (pinfunction "IO5_B9") (pintype "passive"))
    )
    (net (code "31") (name "B14_L17_P") (class "Default")
      (node (ref "JM2") (pin "91") (pinfunction "91_91") (pintype "bidirectional"))
      (node (ref "PCIE-SOUTH") (pin "B8") (pinfunction "IO4_B8") (pintype "passive"))
    )
    (net (code "32") (name "B14_L18_N") (class "Default")
      (node (ref "JM2") (pin "85") (pinfunction "85_85") (pintype "bidirectional"))
      (node (ref "PCIE-SOUTH") (pin "B11") (pinfunction "IO7_B11") (pintype "passive"))
    )
    (net (code "33") (name "B14_L18_P") (class "Default")
      (node (ref "JM2") (pin "87") (pinfunction "87_87") (pintype "bidirectional"))
      (node (ref "PCIE-SOUTH") (pin "B10") (pinfunction "IO6_B10") (pintype "passive"))
    )
    (net (code "34") (name "B14_L19_N") (class "Default")
      (node (ref "JM2") (pin "94") (pinfunction "94_94") (pintype "bidirectional"))
      (node (ref "TP6") (pin "TP") (pinfunction "TP_TP") (pintype "input"))
    )
    (net (code "35") (name "B14_L19_P") (class "Default")
      (node (ref "JM2") (pin "92") (pinfunction "92_92") (pintype "bidirectional"))
      (node (ref "TP5") (pin "TP") (pinfunction "TP_TP") (pintype "input"))
    )
    (net (code "36") (name "B14_L20_N") (class "Default")
      (node (ref "JM2") (pin "95") (pinfunction "95_95") (pintype "bidirectional"))
      (node (ref "PCIE-SOUTH") (pin "B6") (pinfunction "IO2_B6") (pintype "passive"))
    )
    (net (code "37") (name "B14_L20_P") (class "Default")
      (node (ref "JM2") (pin "93") (pinfunction "93_93") (pintype "bidirectional"))
      (node (ref "PCIE-SOUTH") (pin "B7") (pinfunction "IO3_B7") (pintype "passive"))
    )
    (net (code "38") (name "B14_L21_N") (class "Default")
      (node (ref "JM1") (pin "95") (pinfunction "95_95") (pintype "bidirectional"))
      (node (ref "U1") (pin "1") (pinfunction "EN_1") (pintype "input"))
    )
    (net (code "39") (name "B14_L21_P") (class "Default")
      (node (ref "JM1") (pin "93") (pinfunction "93_93") (pintype "bidirectional"))
      (node (ref "U7") (pin "2") (pinfunction "PG_2") (pintype "power_in"))
    )
    (net (code "40") (name "B14_L22_N") (class "Default")
      (node (ref "JM2") (pin "96") (pinfunction "96_96") (pintype "bidirectional"))
      (node (ref "TP7") (pin "TP") (pinfunction "TP_TP") (pintype "input"))
    )
    (net (code "41") (name "B14_L22_P") (class "Default")
      (node (ref "JM2") (pin "98") (pinfunction "98_98") (pintype "bidirectional"))
      (node (ref "TP8") (pin "TP") (pinfunction "TP_TP") (pintype "input"))
    )
    (net (code "42") (name "B14_L23_N") (class "Default")
      (node (ref "JM1") (pin "89") (pinfunction "89_89") (pintype "bidirectional"))
    )
    (net (code "43") (name "B14_L23_P") (class "Default")
      (node (ref "JM1") (pin "91") (pinfunction "91_91") (pintype "bidirectional"))
      (node (ref "U6") (pin "2") (pinfunction "PG_2") (pintype "power_in"))
    )
    (net (code "44") (name "B14_L24_N") (class "Default")
      (node (ref "JM1") (pin "85") (pinfunction "85_85") (pintype "bidirectional"))
    )
    (net (code "45") (name "B14_L24_P") (class "Default")
      (node (ref "JM1") (pin "87") (pinfunction "87_87") (pintype "bidirectional"))
    )
    (net (code "46") (name "B14_L25") (class "Default")
      (node (ref "JM2") (pin "97") (pinfunction "97_97") (pintype "bidirectional"))
      (node (ref "PCIE-SOUTH") (pin "B5") (pinfunction "IO1_B5") (pintype "passive"))
    )
    (net (code "47") (name "B15_L1_N") (class "Default")
      (node (ref "JM2") (pin "14") (pinfunction "14_14") (pintype "bidirectional"))
      (node (ref "PCIE-NORTH") (pin "A14") (pinfunction "LVDS_3B_A14") (pintype "passive"))
    )
    (net (code "48") (name "B15_L1_P") (class "Default")
      (node (ref "JM2") (pin "16") (pinfunction "16_16") (pintype "bidirectional"))
      (node (ref "PCIE-NORTH") (pin "A13") (pinfunction "LVDS_3A_A13") (pintype "passive"))
    )
    (net (code "49") (name "B15_L2_N") (class "Default")
      (node (ref "JM2") (pin "20") (pinfunction "20_20") (pintype "bidirectional"))
    )
    (net (code "50") (name "B15_L2_P") (class "Default")
      (node (ref "JM2") (pin "22") (pinfunction "22_22") (pintype "bidirectional"))
    )
    (net (code "51") (name "B15_L3_N") (class "Default")
      (node (ref "JM2") (pin "4") (pinfunction "4_4") (pintype "bidirectional"))
    )
    (net (code "52") (name "B15_L3_P") (class "Default")
      (node (ref "JM2") (pin "2") (pinfunction "2_2") (pintype "bidirectional"))
    )
    (net (code "53") (name "B15_L4_N") (class "Default")
      (node (ref "JM2") (pin "10") (pinfunction "10_10") (pintype "bidirectional"))
    )
    (net (code "54") (name "B15_L4_P") (class "Default")
      (node (ref "JM2") (pin "12") (pinfunction "12_12") (pintype "bidirectional"))
    )
    (net (code "55") (name "B15_L5_N") (class "Default")
      (node (ref "JM2") (pin "8") (pinfunction "8_8") (pintype "bidirectional"))
      (node (ref "PCIE-NORTH") (pin "A16") (pinfunction "LVDS_4A_A16") (pintype "passive"))
    )
    (net (code "56") (name "B15_L5_P") (class "Default")
      (node (ref "JM2") (pin "6") (pinfunction "6_6") (pintype "bidirectional"))
      (node (ref "PCIE-NORTH") (pin "A17") (pinfunction "LVDS_4B_A17") (pintype "passive"))
    )
    (net (code "57") (name "B15_L6_N") (class "Default")
      (node (ref "JM2") (pin "26") (pinfunction "26_26") (pintype "bidirectional"))
      (node (ref "PCIE-NORTH") (pin "A5") (pinfunction "LVDS_1A_A5") (pintype "passive"))
    )
    (net (code "58") (name "B15_L6_P") (class "Default")
      (node (ref "JM2") (pin "24") (pinfunction "24_24") (pintype "bidirectional"))
      (node (ref "PCIE-NORTH") (pin "A6") (pinfunction "LVDS_1B_A6") (pintype "passive"))
    )
    (net (code "59") (name "B15_L7_N") (class "Default")
      (node (ref "JM2") (pin "1") (pinfunction "1_1") (pintype "bidirectional"))
      (node (ref "PCIE-NORTH") (pin "B17") (pinfunction "LVDS_5B_B17") (pintype "passive"))
    )
    (net (code "60") (name "B15_L7_P") (class "Default")
      (node (ref "JM2") (pin "3") (pinfunction "3_3") (pintype "bidirectional"))
      (node (ref "PCIE-NORTH") (pin "B16") (pinfunction "LVDS_5A_B16") (pintype "passive"))
    )
    (net (code "61") (name "B15_L8_N") (class "Default")
      (node (ref "JM2") (pin "7") (pinfunction "7_7") (pintype "bidirectional"))
    )
    (net (code "62") (name "B15_L8_P") (class "Default")
      (node (ref "JM2") (pin "5") (pinfunction "5_5") (pintype "bidirectional"))
    )
    (net (code "63") (name "B15_L9_N") (class "Default")
      (node (ref "JM2") (pin "15") (pinfunction "15_15") (pintype "bidirectional"))
    )
    (net (code "64") (name "B15_L9_P") (class "Default")
      (node (ref "JM2") (pin "13") (pinfunction "13_13") (pintype "bidirectional"))
    )
    (net (code "65") (name "B15_L10_N") (class "Default")
      (node (ref "JM2") (pin "11") (pinfunction "11_11") (pintype "bidirectional"))
      (node (ref "PCIE-NORTH") (pin "A8") (pinfunction "LVDS_2A_A8") (pintype "passive"))
    )
    (net (code "66") (name "B15_L10_P") (class "Default")
      (node (ref "JM2") (pin "9") (pinfunction "9_9") (pintype "bidirectional"))
      (node (ref "PCIE-NORTH") (pin "A9") (pinfunction "LVDS_2B_A9") (pintype "passive"))
    )
    (net (code "67") (name "B15_L11_N") (class "Default")
      (node (ref "JM2") (pin "30") (pinfunction "30_30") (pintype "bidirectional"))
    )
    (net (code "68") (name "B15_L11_P") (class "Default")
      (node (ref "JM2") (pin "28") (pinfunction "28_28") (pintype "bidirectional"))
    )
    (net (code "69") (name "B15_L12_N") (class "Default")
      (node (ref "JM2") (pin "34") (pinfunction "34_34") (pintype "bidirectional"))
      (node (ref "PCIE-SOUTH") (pin "A8") (pinfunction "LVDS_2A_A8") (pintype "passive"))
    )
    (net (code "70") (name "B15_L12_P") (class "Default")
      (node (ref "JM2") (pin "32") (pinfunction "32_32") (pintype "bidirectional"))
      (node (ref "PCIE-SOUTH") (pin "A9") (pinfunction "LVDS_2B_A9") (pintype "passive"))
    )
    (net (code "71") (name "B15_L13_N") (class "Default")
      (node (ref "JM2") (pin "38") (pinfunction "38_38") (pintype "bidirectional"))
      (node (ref "PCIE-SOUTH") (pin "A6") (pinfunction "LVDS_1B_A6") (pintype "passive"))
    )
    (net (code "72") (name "B15_L13_P") (class "Default")
      (node (ref "JM2") (pin "40") (pinfunction "40_40") (pintype "bidirectional"))
      (node (ref "PCIE-SOUTH") (pin "A5") (pinfunction "LVDS_1A_A5") (pintype "passive"))
    )
    (net (code "73") (name "B15_L14_N") (class "Default")
      (node (ref "JM2") (pin "42") (pinfunction "42_42") (pintype "bidirectional"))
    )
    (net (code "74") (name "B15_L14_P") (class "Default")
      (node (ref "JM2") (pin "44") (pinfunction "44_44") (pintype "bidirectional"))
    )
    (net (code "75") (name "B15_L15_N") (class "Default")
      (node (ref "JM2") (pin "19") (pinfunction "19_19") (pintype "bidirectional"))
      (node (ref "PCIE-NORTH") (pin "A3") (pinfunction "LVDS_0B_A3") (pintype "passive"))
    )
    (net (code "76") (name "B15_L15_P") (class "Default")
      (node (ref "JM2") (pin "21") (pinfunction "21_21") (pintype "bidirectional"))
      (node (ref "PCIE-NORTH") (pin "A2") (pinfunction "LVDS_0A_A2") (pintype "passive"))
    )
    (net (code "77") (name "B15_L16_N") (class "Default")
      (node (ref "JM2") (pin "23") (pinfunction "23_23") (pintype "bidirectional"))
    )
    (net (code "78") (name "B15_L16_P") (class "Default")
      (node (ref "JM2") (pin "25") (pinfunction "25_25") (pintype "bidirectional"))
    )
    (net (code "79") (name "B15_L17_N") (class "Default")
      (node (ref "JM2") (pin "31") (pinfunction "31_31") (pintype "bidirectional"))
    )
    (net (code "80") (name "B15_L17_P") (class "Default")
      (node (ref "JM2") (pin "33") (pinfunction "33_33") (pintype "bidirectional"))
    )
    (net (code "81") (name "B15_L18_N") (class "Default")
      (node (ref "JM2") (pin "27") (pinfunction "27_27") (pintype "bidirectional"))
      (node (ref "PCIE-SOUTH") (pin "A17") (pinfunction "LVDS_4B_A17") (pintype "passive"))
    )
    (net (code "82") (name "B15_L18_P") (class "Default")
      (node (ref "JM2") (pin "29") (pinfunction "29_29") (pintype "bidirectional"))
      (node (ref "PCIE-SOUTH") (pin "A16") (pinfunction "LVDS_4A_A16") (pintype "passive"))
    )
    (net (code "83") (name "B15_L19_N") (class "Default")
      (node (ref "JM2") (pin "41") (pinfunction "41_41") (pintype "bidirectional"))
      (node (ref "PCIE-SOUTH") (pin "B17") (pinfunction "LVDS_5B_B17") (pintype "passive"))
    )
    (net (code "84") (name "B15_L19_P") (class "Default")
      (node (ref "JM2") (pin "43") (pinfunction "43_43") (pintype "bidirectional"))
      (node (ref "PCIE-SOUTH") (pin "B16") (pinfunction "LVDS_5A_B16") (pintype "passive"))
    )
    (net (code "85") (name "B15_L20_N") (class "Default")
      (node (ref "JM2") (pin "50") (pinfunction "50_50") (pintype "bidirectional"))
    )
    (net (code "86") (name "B15_L20_P") (class "Default")
      (node (ref "JM2") (pin "52") (pinfunction "52_52") (pintype "bidirectional"))
    )
    (net (code "87") (name "B15_L21_N") (class "Default")
      (node (ref "JM2") (pin "45") (pinfunction "45_45") (pintype "bidirectional"))
    )
    (net (code "88") (name "B15_L21_P") (class "Default")
      (node (ref "JM2") (pin "47") (pinfunction "47_47") (pintype "bidirectional"))
    )
    (net (code "89") (name "B15_L22_N") (class "Default")
      (node (ref "JM2") (pin "46") (pinfunction "46_46") (pintype "bidirectional"))
      (node (ref "PCIE-SOUTH") (pin "A3") (pinfunction "LVDS_0B_A3") (pintype "passive"))
    )
    (net (code "90") (name "B15_L22_P") (class "Default")
      (node (ref "JM2") (pin "48") (pinfunction "48_48") (pintype "bidirectional"))
      (node (ref "PCIE-SOUTH") (pin "A2") (pinfunction "LVDS_0A_A2") (pintype "passive"))
    )
    (net (code "91") (name "B15_L23_N") (class "Default")
      (node (ref "JM2") (pin "51") (pinfunction "51_51") (pintype "bidirectional"))
      (node (ref "PCIE-SOUTH") (pin "A13") (pinfunction "LVDS_3A_A13") (pintype "passive"))
    )
    (net (code "92") (name "B15_L23_P") (class "Default")
      (node (ref "JM2") (pin "49") (pinfunction "49_49") (pintype "bidirectional"))
      (node (ref "PCIE-SOUTH") (pin "A14") (pinfunction "LVDS_3B_A14") (pintype "passive"))
    )
    (net (code "93") (name "B15_L24_N") (class "Default")
      (node (ref "JM2") (pin "37") (pinfunction "37_37") (pintype "bidirectional"))
    )
    (net (code "94") (name "B15_L24_P") (class "Default")
      (node (ref "JM2") (pin "39") (pinfunction "39_39") (pintype "bidirectional"))
    )
    (net (code "95") (name "B34_L1_N") (class "Default")
      (node (ref "JM1") (pin "37") (pinfunction "37_37") (pintype "bidirectional"))
    )
    (net (code "96") (name "B34_L1_P") (class "Default")
      (node (ref "JM1") (pin "35") (pinfunction "35_35") (pintype "bidirectional"))
    )
    (net (code "97") (name "B34_L2_N") (class "Default")
      (node (ref "JM1") (pin "33") (pinfunction "33_33") (pintype "bidirectional"))
    )
    (net (code "98") (name "B34_L2_P") (class "Default")
      (node (ref "JM1") (pin "31") (pinfunction "31_31") (pintype "bidirectional"))
    )
    (net (code "99") (name "B34_L3_N") (class "Default")
      (node (ref "JM1") (pin "42") (pinfunction "42_42") (pintype "bidirectional"))
      (node (ref "U4") (pin "13") (pinfunction "SCLK_13") (pintype "input"))
    )
    (net (code "100") (name "B34_L3_P") (class "Default")
      (node (ref "JM1") (pin "40") (pinfunction "40_40") (pintype "bidirectional"))
      (node (ref "U4") (pin "17") (pinfunction "GPIO0_17") (pintype "bidirectional"))
    )
    (net (code "101") (name "B34_L4_N") (class "Default")
      (node (ref "JM1") (pin "41") (pinfunction "41_41") (pintype "bidirectional"))
      (node (ref "U4") (pin "12") (pinfunction "SDOUT_12") (pintype "output"))
    )
    (net (code "102") (name "B34_L4_P") (class "Default")
      (node (ref "JM1") (pin "39") (pinfunction "39_39") (pintype "bidirectional"))
    )
    (net (code "103") (name "B34_L5_N") (class "Default")
      (node (ref "JM1") (pin "45") (pinfunction "45_45") (pintype "bidirectional"))
      (node (ref "U4") (pin "10") (pinfunction "~{CS}_10") (pintype "input"))
    )
    (net (code "104") (name "B34_L5_P") (class "Default")
      (node (ref "JM1") (pin "43") (pinfunction "43_43") (pintype "bidirectional"))
      (node (ref "U4") (pin "11") (pinfunction "SDIN_11") (pintype "input"))
    )
    (net (code "105") (name "B34_L6_N") (class "Default")
      (node (ref "JM1") (pin "34") (pinfunction "34_34") (pintype "bidirectional"))
    )
    (net (code "106") (name "B34_L6_P") (class "Default")
      (node (ref "JM1") (pin "32") (pinfunction "32_32") (pintype "bidirectional"))
    )
    (net (code "107") (name "B34_L7_N") (class "Default")
      (node (ref "JM1") (pin "38") (pinfunction "38_38") (pintype "bidirectional"))
      (node (ref "U4") (pin "18") (pinfunction "GPIO1_18") (pintype "bidirectional"))
    )
    (net (code "108") (name "B34_L7_P") (class "Default")
      (node (ref "JM1") (pin "36") (pinfunction "36_36") (pintype "bidirectional"))
    )
    (net (code "109") (name "B34_L8_N") (class "Default")
      (node (ref "JM1") (pin "52") (pinfunction "52_52") (pintype "bidirectional"))
      (node (ref "U3") (pin "13") (pinfunction "SCLK_13") (pintype "input"))
    )
    (net (code "110") (name "B34_L8_P") (class "Default")
      (node (ref "JM1") (pin "50") (pinfunction "50_50") (pintype "bidirectional"))
      (node (ref "U3") (pin "12") (pinfunction "SDOUT_12") (pintype "output"))
    )
    (net (code "111") (name "B34_L9_N") (class "Default")
      (node (ref "JM1") (pin "46") (pinfunction "46_46") (pintype "bidirectional"))
      (node (ref "U4") (pin "33") (pinfunction "GPIO2_33") (pintype "bidirectional"))
    )
    (net (code "112") (name "B34_L9_P") (class "Default")
      (node (ref "JM1") (pin "44") (pinfunction "44_44") (pintype "bidirectional"))
      (node (ref "U4") (pin "36") (pinfunction "GPIO3_36") (pintype "bidirectional"))
    )
    (net (code "113") (name "B34_L10_N") (class "Default")
      (node (ref "JM1") (pin "51") (pinfunction "51_51") (pintype "bidirectional"))
      (node (ref "U5") (pin "11") (pinfunction "SDIN_11") (pintype "input"))
    )
    (net (code "114") (name "B34_L10_P") (class "Default")
      (node (ref "JM1") (pin "49") (pinfunction "49_49") (pintype "bidirectional"))
      (node (ref "U5") (pin "10") (pinfunction "~{CS}_10") (pintype "input"))
    )
    (net (code "115") (name "B34_L11_N") (class "Default")
      (node (ref "JM1") (pin "53") (pinfunction "53_53") (pintype "bidirectional"))
      (node (ref "U5") (pin "12") (pinfunction "SDOUT_12") (pintype "output"))
    )
    (net (code "116") (name "B34_L11_P") (class "Default")
      (node (ref "JM1") (pin "55") (pinfunction "55_55") (pintype "bidirectional"))
      (node (ref "U5") (pin "17") (pinfunction "GPIO0_17") (pintype "bidirectional"))
    )
    (net (code "117") (name "B34_L12_N") (class "Default")
      (node (ref "JM1") (pin "57") (pinfunction "57_57") (pintype "bidirectional"))
      (node (ref "U5") (pin "18") (pinfunction "GPIO1_18") (pintype "bidirectional"))
    )
    (net (code "118") (name "B34_L12_P") (class "Default")
      (node (ref "JM1") (pin "59") (pinfunction "59_59") (pintype "bidirectional"))
      (node (ref "U5") (pin "13") (pinfunction "SCLK_13") (pintype "input"))
    )
    (net (code "119") (name "B34_L13_N") (class "Default")
      (node (ref "JM1") (pin "56") (pinfunction "56_56") (pintype "bidirectional"))
      (node (ref "U3") (pin "18") (pinfunction "GPIO1_18") (pintype "bidirectional"))
    )
    (net (code "120") (name "B34_L13_P") (class "Default")
      (node (ref "JM1") (pin "54") (pinfunction "54_54") (pintype "bidirectional"))
      (node (ref "U3") (pin "17") (pinfunction "GPIO0_17") (pintype "bidirectional"))
    )
    (net (code "121") (name "B34_L14_N") (class "Default")
      (node (ref "JM1") (pin "60") (pinfunction "60_60") (pintype "bidirectional"))
      (node (ref "U3") (pin "36") (pinfunction "GPIO3_36") (pintype "bidirectional"))
    )
    (net (code "122") (name "B34_L14_P") (class "Default")
      (node (ref "JM1") (pin "58") (pinfunction "58_58") (pintype "bidirectional"))
      (node (ref "U3") (pin "33") (pinfunction "GPIO2_33") (pintype "bidirectional"))
    )
    (net (code "123") (name "B34_L15_N") (class "Default")
      (node (ref "JM1") (pin "62") (pinfunction "62_62") (pintype "bidirectional"))
    )
    (net (code "124") (name "B34_L15_P") (class "Default")
      (node (ref "JM1") (pin "64") (pinfunction "64_64") (pintype "bidirectional"))
    )
    (net (code "125") (name "B34_L16_N") (class "Default")
      (node (ref "JM1") (pin "68") (pinfunction "68_68") (pintype "bidirectional"))
    )
    (net (code "126") (name "B34_L16_P") (class "Default")
      (node (ref "JM1") (pin "70") (pinfunction "70_70") (pintype "bidirectional"))
      (node (ref "U4") (pin "32") (pinfunction "RCLK_32") (pintype "input"))
    )
    (net (code "127") (name "B34_L17_N") (class "Default")
      (node (ref "JM1") (pin "63") (pinfunction "63_63") (pintype "bidirectional"))
      (node (ref "U3") (pin "11") (pinfunction "SDIN_11") (pintype "input"))
    )
    (net (code "128") (name "B34_L17_P") (class "Default")
      (node (ref "JM1") (pin "65") (pinfunction "65_65") (pintype "bidirectional"))
      (node (ref "U3") (pin "10") (pinfunction "~{CS}_10") (pintype "input"))
    )
    (net (code "129") (name "B34_L18_N") (class "Default")
      (node (ref "JM1") (pin "74") (pinfunction "74_74") (pintype "bidirectional"))
    )
    (net (code "130") (name "B34_L18_P") (class "Default")
      (node (ref "JM1") (pin "72") (pinfunction "72_72") (pintype "bidirectional"))
    )
    (net (code "131") (name "B34_L19_N") (class "Default")
      (node (ref "JM1") (pin "71") (pinfunction "71_71") (pintype "bidirectional"))
    )
    (net (code "132") (name "B34_L19_P") (class "Default")
      (node (ref "JM1") (pin "73") (pinfunction "73_73") (pintype "bidirectional"))
      (node (ref "U5") (pin "32") (pinfunction "RCLK_32") (pintype "input"))
    )
    (net (code "133") (name "B34_L20_N") (class "Default")
      (node (ref "JM1") (pin "76") (pinfunction "76_76") (pintype "bidirectional"))
      (node (ref "R6") (pin "1") (pinfunction "1_1") (pintype "passive"))
    )
    (net (code "134") (name "B34_L20_P") (class "Default")
      (node (ref "JM1") (pin "78") (pinfunction "78_78") (pintype "bidirectional"))
      (node (ref "R7") (pin "1") (pinfunction "1_1") (pintype "passive"))
    )
    (net (code "135") (name "B34_L21_N") (class "Default")
      (node (ref "JM1") (pin "69") (pinfunction "69_69") (pintype "bidirectional"))
      (node (ref "U5") (pin "33") (pinfunction "GPIO2_33") (pintype "bidirectional"))
    )
    (net (code "136") (name "B34_L21_P") (class "Default")
      (node (ref "JM1") (pin "67") (pinfunction "67_67") (pintype "bidirectional"))
      (node (ref "U5") (pin "36") (pinfunction "GPIO3_36") (pintype "bidirectional"))
    )
    (net (code "137") (name "B34_L22_N") (class "Default")
      (node (ref "JM1") (pin "75") (pinfunction "75_75") (pintype "bidirectional"))
    )
    (net (code "138") (name "B34_L22_P") (class "Default")
      (node (ref "JM1") (pin "77") (pinfunction "77_77") (pintype "bidirectional"))
    )
    (net (code "139") (name "B34_L23_N") (class "Default")
      (node (ref "JM1") (pin "79") (pinfunction "79_79") (pintype "bidirectional"))
    )
    (net (code "140") (name "B34_L23_P") (class "Default")
      (node (ref "JM1") (pin "81") (pinfunction "81_81") (pintype "bidirectional"))
    )
    (net (code "141") (name "B34_L24_N") (class "Default")
      (node (ref "JM1") (pin "80") (pinfunction "80_80") (pintype "bidirectional"))
      (node (ref "R8") (pin "1") (pinfunction "1_1") (pintype "passive"))
    )
    (net (code "142") (name "B34_L24_P") (class "Default")
      (node (ref "JM1") (pin "82") (pinfunction "82_82") (pintype "bidirectional"))
      (node (ref "R9") (pin "1") (pinfunction "1_1") (pintype "passive"))
    )
    (net (code "143") (name "BOOTMODE") (class "Default")
      (node (ref "JM2") (pin "100") (pinfunction "100_100") (pintype "bidirectional"))
    )
    (net (code "144") (name "DONE") (class "Default")
      (node (ref "D5") (pin "A") (pinfunction "A_A") (pintype "passive"))
      (node (ref "JM1") (pin "96") (pinfunction "96_96") (pintype "bidirectional"))
      (node (ref "R4") (pin "1") (pinfunction "1_1") (pintype "passive"))
    )
    (net (code "145") (name "EN_A") (class "Default")
      (node (ref "R18") (pin "1") (pinfunction "1_1") (pintype "passive"))
      (node (ref "U6") (pin "1") (pinfunction "EN_1") (pintype "input"))
    )
    (net (code "146") (name "EN_B") (class "Default")
      (node (ref "R21") (pin "1") (pinfunction "1_1") (pintype "passive"))
      (node (ref "U7") (pin "1") (pinfunction "EN_1") (pintype "input"))
    )
    (net (code "147") (name "GND") (class "Default")
      (node (ref "C1") (pin "2") (pinfunction "2_2") (pintype "passive"))
      (node (ref "C10") (pin "2") (pinfunction "2_2") (pintype "passive"))
      (node (ref "C11") (pin "2") (pinfunction "2_2") (pintype "passive"))
      (node (ref "C12") (pin "2") (pinfunction "2_2") (pintype "passive"))
      (node (ref "C13") (pin "2") (pinfunction "2_2") (pintype "passive"))
      (node (ref "C14") (pin "2") (pinfunction "2_2") (pintype "passive"))
      (node (ref "C15") (pin "2") (pinfunction "2_2") (pintype "passive"))
      (node (ref "C16") (pin "2") (pinfunction "2_2") (pintype "passive"))
      (node (ref "C17") (pin "2") (pinfunction "2_2") (pintype "passive"))
      (node (ref "C18") (pin "2") (pinfunction "2_2") (pintype "passive"))
      (node (ref "C19") (pin "2") (pinfunction "2_2") (pintype "passive"))
      (node (ref "C25") (pin "2") (pinfunction "2_2") (pintype "passive"))
      (node (ref "C26") (pin "2") (pinfunction "2_2") (pintype "passive"))
      (node (ref "C27") (pin "2") (pinfunction "2_2") (pintype "passive"))
      (node (ref "C28") (pin "2") (pinfunction "2_2") (pintype "passive"))
      (node (ref "C29") (pin "2") (pinfunction "2_2") (pintype "passive"))
      (node (ref "C30") (pin "2") (pinfunction "2_2") (pintype "passive"))
      (node (ref "C31") (pin "2") (pinfunction "2_2") (pintype "passive"))
      (node (ref "C32") (pin "2") (pinfunction "2_2") (pintype "passive"))
      (node (ref "C33") (pin "2") (pinfunction "2_2") (pintype "passive"))
      (node (ref "C34") (pin "2") (pinfunction "2_2") (pintype "passive"))
      (node (ref "C35") (pin "2") (pinfunction "2_2") (pintype "passive"))
      (node (ref "C36") (pin "2") (pinfunction "2_2") (pintype "passive"))
      (node (ref "C37") (pin "2") (pinfunction "2_2") (pintype "passive"))
      (node (ref "C4") (pin "2") (pinfunction "2_2") (pintype "passive"))
      (node (ref "C43") (pin "2") (pinfunction "2_2") (pintype "passive"))
      (node (ref "C44") (pin "2") (pinfunction "2_2") (pintype "passive"))
      (node (ref "C45") (pin "2") (pinfunction "2_2") (pintype "passive"))
      (node (ref "C46") (pin "2") (pinfunction "2_2") (pintype "passive"))
      (node (ref "C47") (pin "2") (pinfunction "2_2") (pintype "passive"))
      (node (ref "C48") (pin "2") (pinfunction "2_2") (pintype "passive"))
      (node (ref "C49") (pin "2") (pinfunction "2_2") (pintype "passive"))
      (node (ref "C50") (pin "2") (pinfunction "2_2") (pintype "passive"))
      (node (ref "C51") (pin "2") (pinfunction "2_2") (pintype "passive"))
      (node (ref "C52") (pin "2") (pinfunction "2_2") (pintype "passive"))
      (node (ref "C53") (pin "2") (pinfunction "2_2") (pintype "passive"))
      (node (ref "C54") (pin "2") (pinfunction "2_2") (pintype "passive"))
      (node (ref "C55") (pin "2") (pinfunction "2_2") (pintype "passive"))
      (node (ref "C56") (pin "2") (pinfunction "2_2") (pintype "passive"))
      (node (ref "C57") (pin "2") (pinfunction "2_2") (pintype "passive"))
      (node (ref "C58") (pin "2") (pinfunction "2_2") (pintype "passive"))
      (node (ref "C59") (pin "2") (pinfunction "2_2") (pintype "passive"))
      (node (ref "C8") (pin "2") (pinfunction "2_2") (pintype "passive"))
      (node (ref "C9") (pin "2") (pinfunction "2_2") (pintype "passive"))
      (node (ref "D5") (pin "C") (pinfunction "C_C") (pintype "passive"))
      (node (ref "JM1") (pin "100") (pinfunction "100_100") (pintype "bidirectional"))
      (node (ref "JM1") (pin "11") (pinfunction "11_11") (pintype "bidirectional"))
      (node (ref "JM1") (pin "12") (pinfunction "12_12") (pintype "bidirectional"))
      (node (ref "JM1") (pin "17") (pinfunction "17_17") (pintype "bidirectional"))
      (node (ref "JM1") (pin "18") (pinfunction "18_18") (pintype "bidirectional"))
      (node (ref "JM1") (pin "23") (pinfunction "23_23") (pintype "bidirectional"))
      (node (ref "JM1") (pin "24") (pinfunction "24_24") (pintype "bidirectional"))
      (node (ref "JM1") (pin "29") (pinfunction "29_29") (pintype "bidirectional"))
      (node (ref "JM1") (pin "30") (pinfunction "30_30") (pintype "bidirectional"))
      (node (ref "JM1") (pin "47") (pinfunction "47_47") (pintype "bidirectional"))
      (node (ref "JM1") (pin "48") (pinfunction "48_48") (pintype "bidirectional"))
      (node (ref "JM1") (pin "5") (pinfunction "5_5") (pintype "bidirectional"))
      (node (ref "JM1") (pin "6") (pinfunction "6_6") (pintype "bidirectional"))
      (node (ref "JM1") (pin "66") (pinfunction "66_66") (pintype "bidirectional"))
      (node (ref "JM1") (pin "84") (pinfunction "84_84") (pintype "bidirectional"))
      (node (ref "JM1") (pin "98") (pinfunction "98_98") (pintype "bidirectional"))
      (node (ref "JM1") (pin "F1") (pinfunction "F1_F1") (pintype "bidirectional"))
      (node (ref "JM1") (pin "F2") (pinfunction "F2_F2") (pintype "bidirectional"))
      (node (ref "JM2") (pin "17") (pinfunction "17_17") (pintype "bidirectional"))
      (node (ref "JM2") (pin "35") (pinfunction "35_35") (pintype "bidirectional"))
      (node (ref "JM2") (pin "36") (pinfunction "36_36") (pintype "bidirectional"))
      (node (ref "JM2") (pin "72") (pinfunction "72_72") (pintype "bidirectional"))
      (node (ref "JM2") (pin "83") (pinfunction "83_83") (pintype "bidirectional"))
      (node (ref "JM2") (pin "90") (pinfunction "90_90") (pintype "bidirectional"))
      (node (ref "JM2") (pin "F1") (pinfunction "F1_F1") (pintype "bidirectional"))
      (node (ref "JM2") (pin "F2") (pinfunction "F2_F2") (pintype "bidirectional"))
      (node (ref "JP1") (pin "3") (pinfunction "3_3") (pintype "passive"))
      (node (ref "JTAG") (pin "1") (pinfunction "1_1") (pintype "passive"))
      (node (ref "JTAG") (pin "11") (pinfunction "11_11") (pintype "passive"))
      (node (ref "JTAG") (pin "13") (pinfunction "13_13") (pintype "passive"))
      (node (ref "JTAG") (pin "3") (pinfunction "3_3") (pintype "passive"))
      (node (ref "JTAG") (pin "5") (pinfunction "5_5") (pintype "passive"))
      (node (ref "JTAG") (pin "7") (pinfunction "7_7") (pintype "passive"))
      (node (ref "JTAG") (pin "9") (pinfunction "9_9") (pintype "passive"))
      (node (ref "OUT1") (pin "2@1") (pinfunction "GND_2@1") (pintype "passive"))
      (node (ref "OUT1") (pin "2@2") (pinfunction "GND_2@2") (pintype "passive"))
      (node (ref "OUT1") (pin "2@3") (pinfunction "GND_2@3") (pintype "passive"))
      (node (ref "OUT2") (pin "2@1") (pinfunction "GND_2@1") (pintype "passive"))
      (node (ref "OUT2") (pin "2@2") (pinfunction "GND_2@2") (pintype "passive"))
      (node (ref "OUT2") (pin "2@3") (pinfunction "GND_2@3") (pintype "passive"))
      (node (ref "PCIE-NORTH") (pin "A1") (pinfunction "GND_A1") (pintype "passive"))
      (node (ref "PCIE-NORTH") (pin "A10") (pinfunction "GND_A10") (pintype "passive"))
      (node (ref "PCIE-NORTH") (pin "A12") (pinfunction "GND_A12") (pintype "passive"))
      (node (ref "PCIE-NORTH") (pin "A15") (pinfunction "GND_A15") (pintype "passive"))
      (node (ref "PCIE-NORTH") (pin "A18") (pinfunction "GND_A18") (pintype "passive"))
      (node (ref "PCIE-NORTH") (pin "A4") (pinfunction "GND_A4") (pintype "passive"))
      (node (ref "PCIE-NORTH") (pin "A7") (pinfunction "GND_A7") (pintype "passive"))
      (node (ref "PCIE-NORTH") (pin "B15") (pinfunction "GND_B15") (pintype "passive"))
      (node (ref "PCIE-NORTH") (pin "B18") (pinfunction "GND_B18") (pintype "passive"))
      (node (ref "PCIE-SOUTH") (pin "A1") (pinfunction "GND_A1") (pintype "passive"))
      (node (ref "PCIE-SOUTH") (pin "A10") (pinfunction "GND_A10") (pintype "passive"))
      (node (ref "PCIE-SOUTH") (pin "A12") (pinfunction "GND_A12") (pintype "passive"))
      (node (ref "PCIE-SOUTH") (pin "A15") (pinfunction "GND_A15") (pintype "passive"))
      (node (ref "PCIE-SOUTH") (pin "A18") (pinfunction "GND_A18") (pintype "passive"))
      (node (ref "PCIE-SOUTH") (pin "A4") (pinfunction "GND_A4") (pintype "passive"))
      (node (ref "PCIE-SOUTH") (pin "A7") (pinfunction "GND_A7") (pintype "passive"))
      (node (ref "PCIE-SOUTH") (pin "B15") (pinfunction "GND_B15") (pintype "passive"))
      (node (ref "PCIE-SOUTH") (pin "B18") (pinfunction "GND_B18") (pintype "passive"))
      (node (ref "R10") (pin "2") (pinfunction "2_2") (pintype "passive"))
      (node (ref "R11") (pin "2") (pinfunction "2_2") (pintype "passive"))
      (node (ref "R12") (pin "2") (pinfunction "2_2") (pintype "passive"))
      (node (ref "R13") (pin "2") (pinfunction "2_2") (pintype "passive"))
      (node (ref "R14") (pin "2") (pinfunction "2_2") (pintype "passive"))
      (node (ref "R15") (pin "2") (pinfunction "2_2") (pintype "passive"))
      (node (ref "R16") (pin "2") (pinfunction "2_2") (pintype "passive"))
      (node (ref "R19") (pin "1") (pinfunction "1_1") (pintype "passive"))
      (node (ref "R22") (pin "1") (pinfunction "1_1") (pintype "passive"))
      (node (ref "R3") (pin "2") (pinfunction "2_2") (pintype "passive"))
      (node (ref "SDI-IN") (pin "2@1") (pinfunction "GND_2@1") (pintype "passive"))
      (node (ref "SDI-IN") (pin "2@2") (pinfunction "GND_2@2") (pintype "passive"))
      (node (ref "SDI-IN") (pin "2@3") (pinfunction "GND_2@3") (pintype "passive"))
      (node (ref "U1") (pin "3") (pinfunction "GND_3") (pintype "passive"))
      (node (ref "U2") (pin "1") (pinfunction "A0_1") (pintype "input"))
      (node (ref "U2") (pin "2") (pinfunction "A1_2") (pintype "input"))
      (node (ref "U2") (pin "3") (pinfunction "A2_3") (pintype "input"))
      (node (ref "U2") (pin "4") (pinfunction "GND_4") (pintype "passive"))
      (node (ref "U2") (pin "EP") (pinfunction "EP_EP") (pintype "passive"))
      (node (ref "U3") (pin "1") (pinfunction "VEE_SDI_1") (pintype "power_in"))
      (node (ref "U3") (pin "14") (pinfunction "VSS_14") (pintype "power_in"))
      (node (ref "U3") (pin "15") (pinfunction "VSS_15") (pintype "power_in"))
      (node (ref "U3") (pin "19") (pinfunction "VEE_CORE_19") (pintype "power_in"))
      (node (ref "U3") (pin "21") (pinfunction "VEEO_21") (pintype "power_in"))
      (node (ref "U3") (pin "28") (pinfunction "VEEO_28") (pintype "power_in"))
      (node (ref "U3") (pin "31") (pinfunction "VEE_CORE_31") (pintype "power_in"))
      (node (ref "U3") (pin "37") (pinfunction "VEE_CORE_37") (pintype "power_in"))
      (node (ref "U3") (pin "38") (pinfunction "VEE_CORE_38") (pintype "power_in"))
      (node (ref "U3") (pin "8") (pinfunction "VEE_SDI_8") (pintype "power_in"))
      (node (ref "U4") (pin "1") (pinfunction "VEE_DDI_1") (pintype "power_in"))
      (node (ref "U4") (pin "14") (pinfunction "VSS_14") (pintype "power_in"))
      (node (ref "U4") (pin "15") (pinfunction "VSS_15") (pintype "power_in"))
      (node (ref "U4") (pin "19") (pinfunction "VEE_CORE_19") (pintype "power_in"))
      (node (ref "U4") (pin "21") (pinfunction "VEEO_21") (pintype "power_in"))
      (node (ref "U4") (pin "28") (pinfunction "VEEO_28") (pintype "power_in"))
      (node (ref "U4") (pin "31") (pinfunction "VEE_CORE_31") (pintype "power_in"))
      (node (ref "U4") (pin "37") (pinfunction "VEE_CORE_37") (pintype "power_in"))
      (node (ref "U4") (pin "38") (pinfunction "VEE_CORE_38") (pintype "power_in"))
      (node (ref "U4") (pin "8") (pinfunction "VEE_DDI_8") (pintype "power_in"))
      (node (ref "U5") (pin "1") (pinfunction "VEE_DDI_1") (pintype "power_in"))
      (node (ref "U5") (pin "14") (pinfunction "VSS_14") (pintype "power_in"))
      (node (ref "U5") (pin "15") (pinfunction "VSS_15") (pintype "power_in"))
      (node (ref "U5") (pin "19") (pinfunction "VEE_CORE_19") (pintype "power_in"))
      (node (ref "U5") (pin "21") (pinfunction "VEEO_21") (pintype "power_in"))
      (node (ref "U5") (pin "28") (pinfunction "VEEO_28") (pintype "power_in"))
      (node (ref "U5") (pin "31") (pinfunction "VEE_CORE_31") (pintype "power_in"))
      (node (ref "U5") (pin "37") (pinfunction "VEE_CORE_37") (pintype "power_in"))
      (node (ref "U5") (pin "38") (pinfunction "VEE_CORE_38") (pintype "power_in"))
      (node (ref "U5") (pin "8") (pinfunction "VEE_DDI_8") (pintype "power_in"))
      (node (ref "U6") (pin "5") (pinfunction "GND_5") (pintype "passive"))
      (node (ref "U6") (pin "6") (pinfunction "GND_6") (pintype "passive"))
      (node (ref "U6") (pin "EP") (pinfunction "GND_EP") (pintype "passive"))
      (node (ref "U7") (pin "5") (pinfunction "GND_5") (pintype "passive"))
      (node (ref "U7") (pin "6") (pinfunction "GND_6") (pintype "passive"))
      (node (ref "U7") (pin "EP") (pinfunction "GND_EP") (pintype "passive"))
    )
    (net (code "148") (name "I2C_V") (class "Default")
      (node (ref "C4") (pin "1") (pinfunction "1_1") (pintype "passive"))
      (node (ref "PCIE-NORTH") (pin "B3") (pinfunction "V_I2C_B3") (pintype "passive"))
      (node (ref "R2") (pin "1") (pinfunction "1_1") (pintype "passive"))
      (node (ref "U2") (pin "8") (pinfunction "VCC_8") (pintype "power_in"))
    )
    (net (code "149") (name "MGT_CLK0_N") (class "Default")
      (node (ref "C3") (pin "2") (pinfunction "2_2") (pintype "passive"))
      (node (ref "JM1") (pin "4") (pinfunction "4_4") (pintype "bidirectional"))
    )
    (net (code "150") (name "MGT_CLK0_P") (class "Default")
      (node (ref "C2") (pin "2") (pinfunction "2_2") (pintype "passive"))
      (node (ref "JM1") (pin "2") (pinfunction "2_2") (pintype "bidirectional"))
    )
    (net (code "151") (name "MGT_RX0_N") (class "Default")
      (node (ref "JM1") (pin "21") (pinfunction "21_21") (pintype "bidirectional"))
      (node (ref "U3") (pin "27") (pinfunction "DDO0_27") (pintype "output"))
    )
    (net (code "152") (name "MGT_RX0_P") (class "Default")
      (node (ref "JM1") (pin "19") (pinfunction "19_19") (pintype "bidirectional"))
      (node (ref "U3") (pin "26") (pinfunction "~{DDO0}_26") (pintype "output"))
    )
    (net (code "153") (name "MGT_RX1_N") (class "Default")
      (node (ref "JM1") (pin "15") (pinfunction "15_15") (pintype "bidirectional"))
      (node (ref "U3") (pin "23") (pinfunction "DDO1/RCO_23") (pintype "output"))
    )
    (net (code "154") (name "MGT_RX1_P") (class "Default")
      (node (ref "JM1") (pin "13") (pinfunction "13_13") (pintype "bidirectional"))
      (node (ref "U3") (pin "22") (pinfunction "~{DDO1}/~{RCO}_22") (pintype "output"))
    )
    (net (code "155") (name "MGT_RX2_N") (class "Default")
      (node (ref "JM1") (pin "9") (pinfunction "9_9") (pintype "bidirectional"))
    )
    (net (code "156") (name "MGT_RX2_P") (class "Default")
      (node (ref "JM1") (pin "7") (pinfunction "7_7") (pintype "bidirectional"))
    )
    (net (code "157") (name "MGT_RX3_N") (class "Default")
      (node (ref "JM1") (pin "3") (pinfunction "3_3") (pintype "bidirectional"))
    )
    (net (code "158") (name "MGT_RX3_P") (class "Default")
      (node (ref "JM1") (pin "1") (pinfunction "1_1") (pintype "bidirectional"))
    )
    (net (code "159") (name "MGT_TX0_N") (class "Default")
      (node (ref "JM1") (pin "28") (pinfunction "28_28") (pintype "bidirectional"))
      (node (ref "U5") (pin "6") (pinfunction "DDI_6") (pintype "input"))
    )
    (net (code "160") (name "MGT_TX0_P") (class "Default")
      (node (ref "JM1") (pin "26") (pinfunction "26_26") (pintype "bidirectional"))
      (node (ref "U5") (pin "7") (pinfunction "~{DDI}_7") (pintype "input"))
    )
    (net (code "161") (name "MGT_TX1_N") (class "Default")
      (node (ref "JM1") (pin "22") (pinfunction "22_22") (pintype "bidirectional"))
      (node (ref "U4") (pin "6") (pinfunction "DDI_6") (pintype "input"))
    )
    (net (code "162") (name "MGT_TX1_P") (class "Default")
      (node (ref "JM1") (pin "20") (pinfunction "20_20") (pintype "bidirectional"))
      (node (ref "U4") (pin "7") (pinfunction "~{DDI}_7") (pintype "input"))
    )
    (net (code "163") (name "MGT_TX2_N") (class "Default")
      (node (ref "JM1") (pin "16") (pinfunction "16_16") (pintype "bidirectional"))
    )
    (net (code "164") (name "MGT_TX2_P") (class "Default")
      (node (ref "JM1") (pin "14") (pinfunction "14_14") (pintype "bidirectional"))
    )
    (net (code "165") (name "MGT_TX3_N") (class "Default")
      (node (ref "JM1") (pin "10") (pinfunction "10_10") (pintype "bidirectional"))
    )
    (net (code "166") (name "MGT_TX3_P") (class "Default")
      (node (ref "JM1") (pin "8") (pinfunction "8_8") (pintype "bidirectional"))
    )
    (net (code "167") (name "M_1V8") (class "Default")
      (node (ref "JM2") (pin "18") (pinfunction "18_18") (pintype "bidirectional"))
      (node (ref "R5") (pin "2") (pinfunction "2_2") (pintype "passive"))
    )
    (net (code "168") (name "N_5V") (class "Default")
      (node (ref "PCIE-NORTH") (pin "B12") (pinfunction "5V_B12") (pintype "passive"))
    )
    (net (code "169") (name "N_IO0") (class "Default")
      (node (ref "PCIE-NORTH") (pin "B4") (pinfunction "IO0_B4") (pintype "passive"))
    )
    (net (code "170") (name "N_IO1") (class "Default")
      (node (ref "PCIE-NORTH") (pin "B5") (pinfunction "IO1_B5") (pintype "passive"))
    )
    (net (code "171") (name "N_IO2") (class "Default")
      (node (ref "PCIE-NORTH") (pin "B6") (pinfunction "IO2_B6") (pintype "passive"))
    )
    (net (code "172") (name "N_IO3") (class "Default")
      (node (ref "PCIE-NORTH") (pin "B7") (pinfunction "IO3_B7") (pintype "passive"))
    )
    (net (code "173") (name "N_IO4") (class "Default")
      (node (ref "PCIE-NORTH") (pin "B8") (pinfunction "IO4_B8") (pintype "passive"))
    )
    (net (code "174") (name "N_IO5") (class "Default")
      (node (ref "PCIE-NORTH") (pin "B9") (pinfunction "IO5_B9") (pintype "passive"))
    )
    (net (code "175") (name "N_IO6") (class "Default")
      (node (ref "PCIE-NORTH") (pin "B10") (pinfunction "IO6_B10") (pintype "passive"))
    )
    (net (code "176") (name "N_IO7") (class "Default")
      (node (ref "PCIE-NORTH") (pin "B11") (pinfunction "IO7_B11") (pintype "passive"))
    )
    (net (code "177") (name "N_PCIE_V") (class "Default")
      (node (ref "PCIE-NORTH") (pin "B13") (pinfunction "VCC_B13") (pintype "passive"))
    )
    (net (code "178") (name "N_VCCIO") (class "Default")
      (node (ref "PCIE-NORTH") (pin "B14") (pinfunction "VCCIO_B14") (pintype "passive"))
    )
    (net (code "179") (name "Net-(C5-Pad1)") (class "Default")
      (node (ref "C5") (pin "1") (pinfunction "1_1") (pintype "passive"))
      (node (ref "SDI-IN") (pin "1") (pinfunction "1_1") (pintype "passive"))
    )
    (net (code "180") (name "Net-(C7-Pad2)") (class "Default")
      (node (ref "C7") (pin "2") (pinfunction "2_2") (pintype "passive"))
      (node (ref "R10") (pin "1") (pinfunction "1_1") (pintype "passive"))
    )
    (net (code "181") (name "Net-(C20-Pad2)") (class "Default")
      (node (ref "C20") (pin "2") (pinfunction "2_2") (pintype "passive"))
      (node (ref "OUT1") (pin "1") (pinfunction "1_1") (pintype "passive"))
    )
    (net (code "182") (name "Net-(C21-Pad2)") (class "Default")
      (node (ref "C21") (pin "2") (pinfunction "2_2") (pintype "passive"))
      (node (ref "R11") (pin "1") (pinfunction "1_1") (pintype "passive"))
    )
    (net (code "183") (name "Net-(C22-Pad2)") (class "Default")
      (node (ref "C22") (pin "2") (pinfunction "2_2") (pintype "passive"))
      (node (ref "R12") (pin "1") (pinfunction "1_1") (pintype "passive"))
    )
    (net (code "184") (name "Net-(C23-Pad2)") (class "Default")
      (node (ref "C23") (pin "2") (pinfunction "2_2") (pintype "passive"))
      (node (ref "R13") (pin "1") (pinfunction "1_1") (pintype "passive"))
    )
    (net (code "185") (name "Net-(C38-Pad2)") (class "Default")
      (node (ref "C38") (pin "2") (pinfunction "2_2") (pintype "passive"))
      (node (ref "OUT2") (pin "1") (pinfunction "1_1") (pintype "passive"))
    )
    (net (code "186") (name "Net-(C39-Pad2)") (class "Default")
      (node (ref "C39") (pin "2") (pinfunction "2_2") (pintype "passive"))
      (node (ref "R14") (pin "1") (pinfunction "1_1") (pintype "passive"))
    )
    (net (code "187") (name "Net-(C40-Pad2)") (class "Default")
      (node (ref "C40") (pin "2") (pinfunction "2_2") (pintype "passive"))
      (node (ref "R15") (pin "1") (pinfunction "1_1") (pintype "passive"))
    )
    (net (code "188") (name "Net-(C41-Pad2)") (class "Default")
      (node (ref "C41") (pin "2") (pinfunction "2_2") (pintype "passive"))
      (node (ref "R16") (pin "1") (pinfunction "1_1") (pintype "passive"))
    )
    (net (code "189") (name "Net-(D1-PadC)") (class "Default")
      (node (ref "D1") (pin "C") (pinfunction "C_C") (pintype "passive"))
      (node (ref "R6") (pin "2") (pinfunction "2_2") (pintype "passive"))
    )
    (net (code "190") (name "Net-(D2-PadC)") (class "Default")
      (node (ref "D2") (pin "C") (pinfunction "C_C") (pintype "passive"))
      (node (ref "R7") (pin "2") (pinfunction "2_2") (pintype "passive"))
    )
    (net (code "191") (name "Net-(D3-PadC)") (class "Default")
      (node (ref "D3") (pin "C") (pinfunction "C_C") (pintype "passive"))
      (node (ref "R8") (pin "2") (pinfunction "2_2") (pintype "passive"))
    )
    (net (code "192") (name "Net-(D4-PadC)") (class "Default")
      (node (ref "D4") (pin "C") (pinfunction "C_C") (pintype "passive"))
      (node (ref "R9") (pin "2") (pinfunction "2_2") (pintype "passive"))
    )
    (net (code "193") (name "Net-(U1-OUT+)") (class "Default")
      (node (ref "C2") (pin "1") (pinfunction "1_1") (pintype "passive"))
      (node (ref "R1") (pin "1") (pinfunction "1_1") (pintype "passive"))
      (node (ref "U1") (pin "4") (pinfunction "OUT+_4") (pintype "output"))
    )
    (net (code "194") (name "Net-(U1-OUT-)") (class "Default")
      (node (ref "C3") (pin "1") (pinfunction "1_1") (pintype "passive"))
      (node (ref "R1") (pin "2") (pinfunction "2_2") (pintype "passive"))
      (node (ref "U1") (pin "5") (pinfunction "OUT-_5") (pintype "output"))
    )
    (net (code "195") (name "Net-(U2-WP)") (class "Default")
      (node (ref "R2") (pin "2") (pinfunction "2_2") (pintype "passive"))
      (node (ref "R3") (pin "1") (pinfunction "1_1") (pintype "passive"))
      (node (ref "U2") (pin "7") (pinfunction "WP_7") (pintype "input"))
    )
    (net (code "196") (name "Net-(U3-LF+)") (class "Default")
      (node (ref "C6") (pin "1") (pinfunction "1_1") (pintype "passive"))
      (node (ref "U3") (pin "39") (pinfunction "LF+_39") (pintype "passive"))
    )
    (net (code "197") (name "Net-(U3-LF-)") (class "Default")
      (node (ref "C6") (pin "2") (pinfunction "2_2") (pintype "passive"))
      (node (ref "U3") (pin "40") (pinfunction "LF-_40") (pintype "passive"))
    )
    (net (code "198") (name "Net-(U3-SDI)") (class "Default")
      (node (ref "C5") (pin "2") (pinfunction "2_2") (pintype "passive"))
      (node (ref "U3") (pin "2") (pinfunction "SDI_2") (pintype "input"))
    )
    (net (code "199") (name "Net-(U3-SDI_TERM)") (class "Default")
      (node (ref "C7") (pin "1") (pinfunction "1_1") (pintype "passive"))
      (node (ref "U3") (pin "3") (pinfunction "SDI_TERM_3") (pintype "passive"))
    )
    (net (code "200") (name "Net-(U3-VCO_FILT)") (class "Default")
      (node (ref "C8") (pin "1") (pinfunction "1_1") (pintype "passive"))
      (node (ref "U3") (pin "34") (pinfunction "VCO_FILT_34") (pintype "passive"))
    )
    (net (code "201") (name "Net-(U3-VCO_FILT10)") (class "Default")
      (node (ref "C9") (pin "1") (pinfunction "1_1") (pintype "passive"))
      (node (ref "U3") (pin "30") (pinfunction "VCO_FILT10_30") (pintype "passive"))
    )
    (net (code "202") (name "Net-(U4-LF+)") (class "Default")
      (node (ref "C24") (pin "1") (pinfunction "1_1") (pintype "passive"))
      (node (ref "U4") (pin "39") (pinfunction "LF+_39") (pintype "passive"))
    )
    (net (code "203") (name "Net-(U4-LF-)") (class "Default")
      (node (ref "C24") (pin "2") (pinfunction "2_2") (pintype "passive"))
      (node (ref "U4") (pin "40") (pinfunction "LF-_40") (pintype "passive"))
    )
    (net (code "204") (name "Net-(U4-SDO0)") (class "Default")
      (node (ref "C20") (pin "1") (pinfunction "1_1") (pintype "passive"))
      (node (ref "U4") (pin "27") (pinfunction "SDO0_27") (pintype "output"))
    )
    (net (code "205") (name "Net-(U4-SDO1{slash}RCO)") (class "Default")
      (node (ref "C22") (pin "1") (pinfunction "1_1") (pintype "passive"))
      (node (ref "U4") (pin "23") (pinfunction "SDO1/RCO_23") (pintype "output"))
    )
    (net (code "206") (name "Net-(U4-TERM)") (class "Default")
      (node (ref "C25") (pin "1") (pinfunction "1_1") (pintype "passive"))
      (node (ref "U4") (pin "5") (pinfunction "TERM_5") (pintype "passive"))
    )
    (net (code "207") (name "Net-(U4-VCO_FILT)") (class "Default")
      (node (ref "C26") (pin "1") (pinfunction "1_1") (pintype "passive"))
      (node (ref "U4") (pin "34") (pinfunction "VCO_FILT_34") (pintype "passive"))
    )
    (net (code "208") (name "Net-(U4-VCO_FILT10)") (class "Default")
      (node (ref "C27") (pin "1") (pinfunction "1_1") (pintype "passive"))
      (node (ref "U4") (pin "30") (pinfunction "VCO_FILT10_30") (pintype "passive"))
    )
    (net (code "209") (name "Net-(U4-~{SDO0})") (class "Default")
      (node (ref "C23") (pin "1") (pinfunction "1_1") (pintype "passive"))
      (node (ref "U4") (pin "26") (pinfunction "~{SDO0}_26") (pintype "output"))
    )
    (net (code "210") (name "Net-(U4-~{SDO1}{slash}~{RCO})") (class "Default")
      (node (ref "C21") (pin "1") (pinfunction "1_1") (pintype "passive"))
      (node (ref "U4") (pin "22") (pinfunction "~{SDO1}/~{RCO}_22") (pintype "output"))
    )
    (net (code "211") (name "Net-(U5-LF+)") (class "Default")
      (node (ref "C42") (pin "1") (pinfunction "1_1") (pintype "passive"))
      (node (ref "U5") (pin "39") (pinfunction "LF+_39") (pintype "passive"))
    )
    (net (code "212") (name "Net-(U5-LF-)") (class "Default")
      (node (ref "C42") (pin "2") (pinfunction "2_2") (pintype "passive"))
      (node (ref "U5") (pin "40") (pinfunction "LF-_40") (pintype "passive"))
    )
    (net (code "213") (name "Net-(U5-SDO0)") (class "Default")
      (node (ref "C41") (pin "1") (pinfunction "1_1") (pintype "passive"))
      (node (ref "U5") (pin "27") (pinfunction "SDO0_27") (pintype "output"))
    )
    (net (code "214") (name "Net-(U5-SDO1{slash}RCO)") (class "Default")
      (node (ref "C38") (pin "1") (pinfunction "1_1") (pintype "passive"))
      (node (ref "U5") (pin "23") (pinfunction "SDO1/RCO_23") (pintype "output"))
    )
    (net (code "215") (name "Net-(U5-TERM)") (class "Default")
      (node (ref "C43") (pin "1") (pinfunction "1_1") (pintype "passive"))
      (node (ref "U5") (pin "5") (pinfunction "TERM_5") (pintype "passive"))
    )
    (net (code "216") (name "Net-(U5-VCO_FILT)") (class "Default")
      (node (ref "C44") (pin "1") (pinfunction "1_1") (pintype "passive"))
      (node (ref "U5") (pin "34") (pinfunction "VCO_FILT_34") (pintype "passive"))
    )
    (net (code "217") (name "Net-(U5-VCO_FILT10)") (class "Default")
      (node (ref "C45") (pin "1") (pinfunction "1_1") (pintype "passive"))
      (node (ref "U5") (pin "30") (pinfunction "VCO_FILT10_30") (pintype "passive"))
    )
    (net (code "218") (name "Net-(U5-~{SDO0})") (class "Default")
      (node (ref "C40") (pin "1") (pinfunction "1_1") (pintype "passive"))
      (node (ref "U5") (pin "26") (pinfunction "~{SDO0}_26") (pintype "output"))
    )
    (net (code "219") (name "Net-(U5-~{SDO1}{slash}~{RCO})") (class "Default")
      (node (ref "C39") (pin "1") (pinfunction "1_1") (pintype "passive"))
      (node (ref "U5") (pin "22") (pinfunction "~{SDO1}/~{RCO}_22") (pintype "output"))
    )
    (net (code "220") (name "Net-(U6-FB)") (class "Default")
      (node (ref "R17") (pin "1") (pinfunction "1_1") (pintype "passive"))
      (node (ref "R19") (pin "2") (pinfunction "2_2") (pintype "passive"))
      (node (ref "U6") (pin "7") (pinfunction "FB_7") (pintype "output"))
    )
    (net (code "221") (name "Net-(U7-FB)") (class "Default")
      (node (ref "R20") (pin "1") (pinfunction "1_1") (pintype "passive"))
      (node (ref "R22") (pin "2") (pinfunction "2_2") (pintype "passive"))
      (node (ref "U7") (pin "7") (pinfunction "FB_7") (pintype "output"))
    )
    (net (code "222") (name "PROG_B") (class "Default")
      (node (ref "JM1") (pin "94") (pinfunction "94_94") (pintype "bidirectional"))
    )
    (net (code "223") (name "SCL") (class "Default")
      (node (ref "PCIE-NORTH") (pin "B2") (pinfunction "SCL_B2") (pintype "passive"))
      (node (ref "U2") (pin "6") (pinfunction "SCL_6") (pintype "input"))
    )
    (net (code "224") (name "SDA") (class "Default")
      (node (ref "PCIE-NORTH") (pin "B1") (pinfunction "SDA_B1") (pintype "passive"))
      (node (ref "U2") (pin "5") (pinfunction "SDA_5") (pintype "bidirectional"))
    )
    (net (code "225") (name "SPI-CLK") (class "Default")
      (node (ref "JM2") (pin "67") (pinfunction "67_67") (pintype "bidirectional"))
    )
    (net (code "226") (name "SPI-CS") (class "Default")
      (node (ref "JM2") (pin "69") (pinfunction "69_69") (pintype "bidirectional"))
    )
    (net (code "227") (name "SPI-DQ0") (class "Default")
      (node (ref "JM2") (pin "68") (pinfunction "68_68") (pintype "bidirectional"))
    )
    (net (code "228") (name "SPI-DQ1") (class "Default")
      (node (ref "JM2") (pin "71") (pinfunction "71_71") (pintype "bidirectional"))
    )
    (net (code "229") (name "SPI-DQ2") (class "Default")
      (node (ref "JM2") (pin "73") (pinfunction "73_73") (pintype "bidirectional"))
    )
    (net (code "230") (name "SPI-DQ3") (class "Default")
      (node (ref "JM2") (pin "70") (pinfunction "70_70") (pintype "bidirectional"))
    )
    (net (code "231") (name "S_5V") (class "Default")
      (node (ref "JP1") (pin "1") (pinfunction "1_1") (pintype "passive"))
      (node (ref "PCIE-SOUTH") (pin "B12") (pinfunction "5V_B12") (pintype "passive"))
    )
    (net (code "232") (name "S_PCIE_V") (class "Default")
      (node (ref "PCIE-SOUTH") (pin "B13") (pinfunction "VCC_B13") (pintype "passive"))
    )
    (net (code "233") (name "S_VCCIO") (class "Default")
      (node (ref "JM2") (pin "54") (pinfunction "54_54") (pintype "bidirectional"))
      (node (ref "PCIE-SOUTH") (pin "B14") (pinfunction "VCCIO_B14") (pintype "passive"))
    )
    (net (code "234") (name "TCK") (class "Default")
      (node (ref "JM1") (pin "90") (pinfunction "90_90") (pintype "bidirectional"))
      (node (ref "JTAG") (pin "6") (pinfunction "6_6") (pintype "passive"))
    )
    (net (code "235") (name "TDI") (class "Default")
      (node (ref "JM1") (pin "86") (pinfunction "86_86") (pintype "bidirectional"))
      (node (ref "JTAG") (pin "10") (pinfunction "10_10") (pintype "passive"))
    )
    (net (code "236") (name "TDO") (class "Default")
      (node (ref "JM1") (pin "88") (pinfunction "88_88") (pintype "bidirectional"))
      (node (ref "JTAG") (pin "8") (pinfunction "8_8") (pintype "passive"))
    )
    (net (code "237") (name "TMS") (class "Default")
      (node (ref "JM1") (pin "92") (pinfunction "92_92") (pintype "bidirectional"))
      (node (ref "JTAG") (pin "4") (pinfunction "4_4") (pintype "passive"))
    )
    (net (code "238") (name "VCCIO0") (class "Default")
      (node (ref "JM2") (pin "53") (pinfunction "53_53") (pintype "bidirectional"))
      (node (ref "JTAG") (pin "2") (pinfunction "2_2") (pintype "passive"))
    )
    (net (code "239") (name "VCCIO14") (class "Default")
      (node (ref "JM1") (pin "83") (pinfunction "83_83") (pintype "bidirectional"))
    )
    (net (code "240") (name "VCCO_4") (class "Default")
      (node (ref "C17") (pin "1") (pinfunction "1_1") (pintype "passive"))
      (node (ref "C18") (pin "1") (pinfunction "1_1") (pintype "passive"))
      (node (ref "C19") (pin "1") (pinfunction "1_1") (pintype "passive"))
      (node (ref "FB4") (pin "2") (pinfunction "2_2") (pintype "passive"))
      (node (ref "U3") (pin "24") (pinfunction "VCCO_1_24") (pintype "power_in"))
      (node (ref "U3") (pin "25") (pinfunction "VCCO_0_25") (pintype "power_in"))
    )
    (net (code "241") (name "VCCO_8") (class "Default")
      (node (ref "C35") (pin "1") (pinfunction "1_1") (pintype "passive"))
      (node (ref "C36") (pin "1") (pinfunction "1_1") (pintype "passive"))
      (node (ref "C37") (pin "1") (pinfunction "1_1") (pintype "passive"))
      (node (ref "FB7") (pin "2") (pinfunction "2_2") (pintype "passive"))
      (node (ref "U4") (pin "24") (pinfunction "VCCO_1_24") (pintype "power_in"))
      (node (ref "U4") (pin "25") (pinfunction "VCCO_0_25") (pintype "power_in"))
    )
    (net (code "242") (name "VCCO_9") (class "Default")
      (node (ref "C53") (pin "1") (pinfunction "1_1") (pintype "passive"))
      (node (ref "C54") (pin "1") (pinfunction "1_1") (pintype "passive"))
      (node (ref "C55") (pin "1") (pinfunction "1_1") (pintype "passive"))
      (node (ref "FB10") (pin "2") (pinfunction "2_2") (pintype "passive"))
      (node (ref "U5") (pin "24") (pinfunction "VCCO_1_24") (pintype "power_in"))
      (node (ref "U5") (pin "25") (pinfunction "VCCO_0_25") (pintype "power_in"))
    )
    (net (code "243") (name "VCC_4") (class "Default")
      (node (ref "C14") (pin "1") (pinfunction "1_1") (pintype "passive"))
      (node (ref "C15") (pin "1") (pinfunction "1_1") (pintype "passive"))
      (node (ref "C16") (pin "1") (pinfunction "1_1") (pintype "passive"))
      (node (ref "FB3") (pin "2") (pinfunction "2_2") (pintype "passive"))
      (node (ref "U3") (pin "35") (pinfunction "VCC_CORE_35") (pintype "power_in"))
      (node (ref "U3") (pin "4") (pinfunction "VCC_SDI_4") (pintype "power_in"))
    )
    (net (code "244") (name "VCC_8") (class "Default")
      (node (ref "C32") (pin "1") (pinfunction "1_1") (pintype "passive"))
      (node (ref "C33") (pin "1") (pinfunction "1_1") (pintype "passive"))
      (node (ref "C34") (pin "1") (pinfunction "1_1") (pintype "passive"))
      (node (ref "FB6") (pin "2") (pinfunction "2_2") (pintype "passive"))
      (node (ref "U4") (pin "35") (pinfunction "VCC_CORE_35") (pintype "power_in"))
      (node (ref "U4") (pin "4") (pinfunction "VCC_DDI_4") (pintype "power_in"))
    )
    (net (code "245") (name "VCC_9") (class "Default")
      (node (ref "C50") (pin "1") (pinfunction "1_1") (pintype "passive"))
      (node (ref "C51") (pin "1") (pinfunction "1_1") (pintype "passive"))
      (node (ref "C52") (pin "1") (pinfunction "1_1") (pintype "passive"))
      (node (ref "FB9") (pin "2") (pinfunction "2_2") (pintype "passive"))
      (node (ref "U5") (pin "35") (pinfunction "VCC_CORE_35") (pintype "power_in"))
      (node (ref "U5") (pin "4") (pinfunction "VCC_DDI_4") (pintype "power_in"))
    )
    (net (code "246") (name "VDD_4") (class "Default")
      (node (ref "C10") (pin "1") (pinfunction "1_1") (pintype "passive"))
      (node (ref "C11") (pin "1") (pinfunction "1_1") (pintype "passive"))
      (node (ref "C12") (pin "1") (pinfunction "1_1") (pintype "passive"))
      (node (ref "C13") (pin "1") (pinfunction "1_1") (pintype "passive"))
      (node (ref "FB2") (pin "2") (pinfunction "2_2") (pintype "passive"))
      (node (ref "U3") (pin "16") (pinfunction "VDD_16") (pintype "power_in"))
      (node (ref "U3") (pin "20") (pinfunction "VCCO1V8_1_20") (pintype "power_in"))
      (node (ref "U3") (pin "29") (pinfunction "VCCO1V8_0_29") (pintype "power_in"))
    )
    (net (code "247") (name "VDD_8") (class "Default")
      (node (ref "C28") (pin "1") (pinfunction "1_1") (pintype "passive"))
      (node (ref "C29") (pin "1") (pinfunction "1_1") (pintype "passive"))
      (node (ref "C30") (pin "1") (pinfunction "1_1") (pintype "passive"))
      (node (ref "C31") (pin "1") (pinfunction "1_1") (pintype "passive"))
      (node (ref "FB5") (pin "2") (pinfunction "2_2") (pintype "passive"))
      (node (ref "U4") (pin "16") (pinfunction "VDD_16") (pintype "power_in"))
      (node (ref "U4") (pin "20") (pinfunction "VCCO1V8_1_20") (pintype "power_in"))
      (node (ref "U4") (pin "29") (pinfunction "VCCO1V8_0_29") (pintype "power_in"))
    )
    (net (code "248") (name "VDD_9") (class "Default")
      (node (ref "C46") (pin "1") (pinfunction "1_1") (pintype "passive"))
      (node (ref "C47") (pin "1") (pinfunction "1_1") (pintype "passive"))
      (node (ref "C48") (pin "1") (pinfunction "1_1") (pintype "passive"))
      (node (ref "C49") (pin "1") (pinfunction "1_1") (pintype "passive"))
      (node (ref "FB8") (pin "2") (pinfunction "2_2") (pintype "passive"))
      (node (ref "U5") (pin "16") (pinfunction "VDD_16") (pintype "power_in"))
      (node (ref "U5") (pin "20") (pinfunction "VCCO1V8_1_20") (pintype "power_in"))
      (node (ref "U5") (pin "29") (pinfunction "VCCO1V8_0_29") (pintype "power_in"))
    )
    (net (code "249") (name "VOUT_A") (class "Default")
      (node (ref "C57") (pin "1") (pinfunction "1_1") (pintype "passive"))
      (node (ref "FB11") (pin "1") (pinfunction "1_1") (pintype "passive"))
      (node (ref "R17") (pin "2") (pinfunction "2_2") (pintype "passive"))
      (node (ref "U6") (pin "8") (pinfunction "VOUT_8") (pintype "output"))
    )
    (net (code "250") (name "VOUT_B") (class "Default")
      (node (ref "C59") (pin "1") (pinfunction "1_1") (pintype "passive"))
      (node (ref "FB12") (pin "1") (pinfunction "1_1") (pintype "passive"))
      (node (ref "R20") (pin "2") (pinfunction "2_2") (pintype "passive"))
      (node (ref "U7") (pin "8") (pinfunction "VOUT_8") (pintype "output"))
    )
    (net (code "251") (name "VSUP") (class "Default")
      (node (ref "C56") (pin "1") (pinfunction "1_1") (pintype "passive"))
      (node (ref "C58") (pin "1") (pinfunction "1_1") (pintype "passive"))
      (node (ref "JP1") (pin "2") (pinfunction "2_2") (pintype "passive"))
      (node (ref "R18") (pin "2") (pinfunction "2_2") (pintype "passive"))
      (node (ref "R21") (pin "2") (pinfunction "2_2") (pintype "passive"))
      (node (ref "U6") (pin "3") (pinfunction "VIN_3") (pintype "power_in"))
      (node (ref "U6") (pin "4") (pinfunction "VIN_4") (pintype "power_in"))
      (node (ref "U7") (pin "3") (pinfunction "VIN_3") (pintype "power_in"))
      (node (ref "U7") (pin "4") (pinfunction "VIN_4") (pintype "power_in"))
    )
    (net (code "252") (name "V_CLK") (class "Default")
      (node (ref "C1") (pin "1") (pinfunction "1_1") (pintype "passive"))
      (node (ref "FB1") (pin "2") (pinfunction "2_2") (pintype "passive"))
      (node (ref "U1") (pin "6") (pinfunction "VCC_6") (pintype "power_in"))
    )
    (net (code "253") (name "unconnected-(JTAG-Pad12)") (class "Default")
      (node (ref "JTAG") (pin "12") (pinfunction "12_12") (pintype "passive"))
    )
    (net (code "254") (name "unconnected-(JTAG-Pad14)") (class "Default")
      (node (ref "JTAG") (pin "14") (pinfunction "14_14") (pintype "passive"))
    )
    (net (code "255") (name "unconnected-(PCIE-NORTH-PWRGD-PadA11)") (class "Default")
      (node (ref "PCIE-NORTH") (pin "A11") (pinfunction "PWRGD_A11") (pintype "passive"))
    )
    (net (code "256") (name "unconnected-(PCIE-SOUTH-PWRGD-PadA11)") (class "Default")
      (node (ref "PCIE-SOUTH") (pin "A11") (pinfunction "PWRGD_A11") (pintype "passive"))
    )
    (net (code "257") (name "unconnected-(PCIE-SOUTH-SCL-PadB2)") (class "Default")
      (node (ref "PCIE-SOUTH") (pin "B2") (pinfunction "SCL_B2") (pintype "passive"))
    )
    (net (code "258") (name "unconnected-(PCIE-SOUTH-SDA-PadB1)") (class "Default")
      (node (ref "PCIE-SOUTH") (pin "B1") (pinfunction "SDA_B1") (pintype "passive"))
    )
    (net (code "259") (name "unconnected-(PCIE-SOUTH-V_I2C-PadB3)") (class "Default")
      (node (ref "PCIE-SOUTH") (pin "B3") (pinfunction "V_I2C_B3") (pintype "passive"))
    )
  )
)
